# Basic.net
KiCad netlist of a schematic drawn in EAGLE
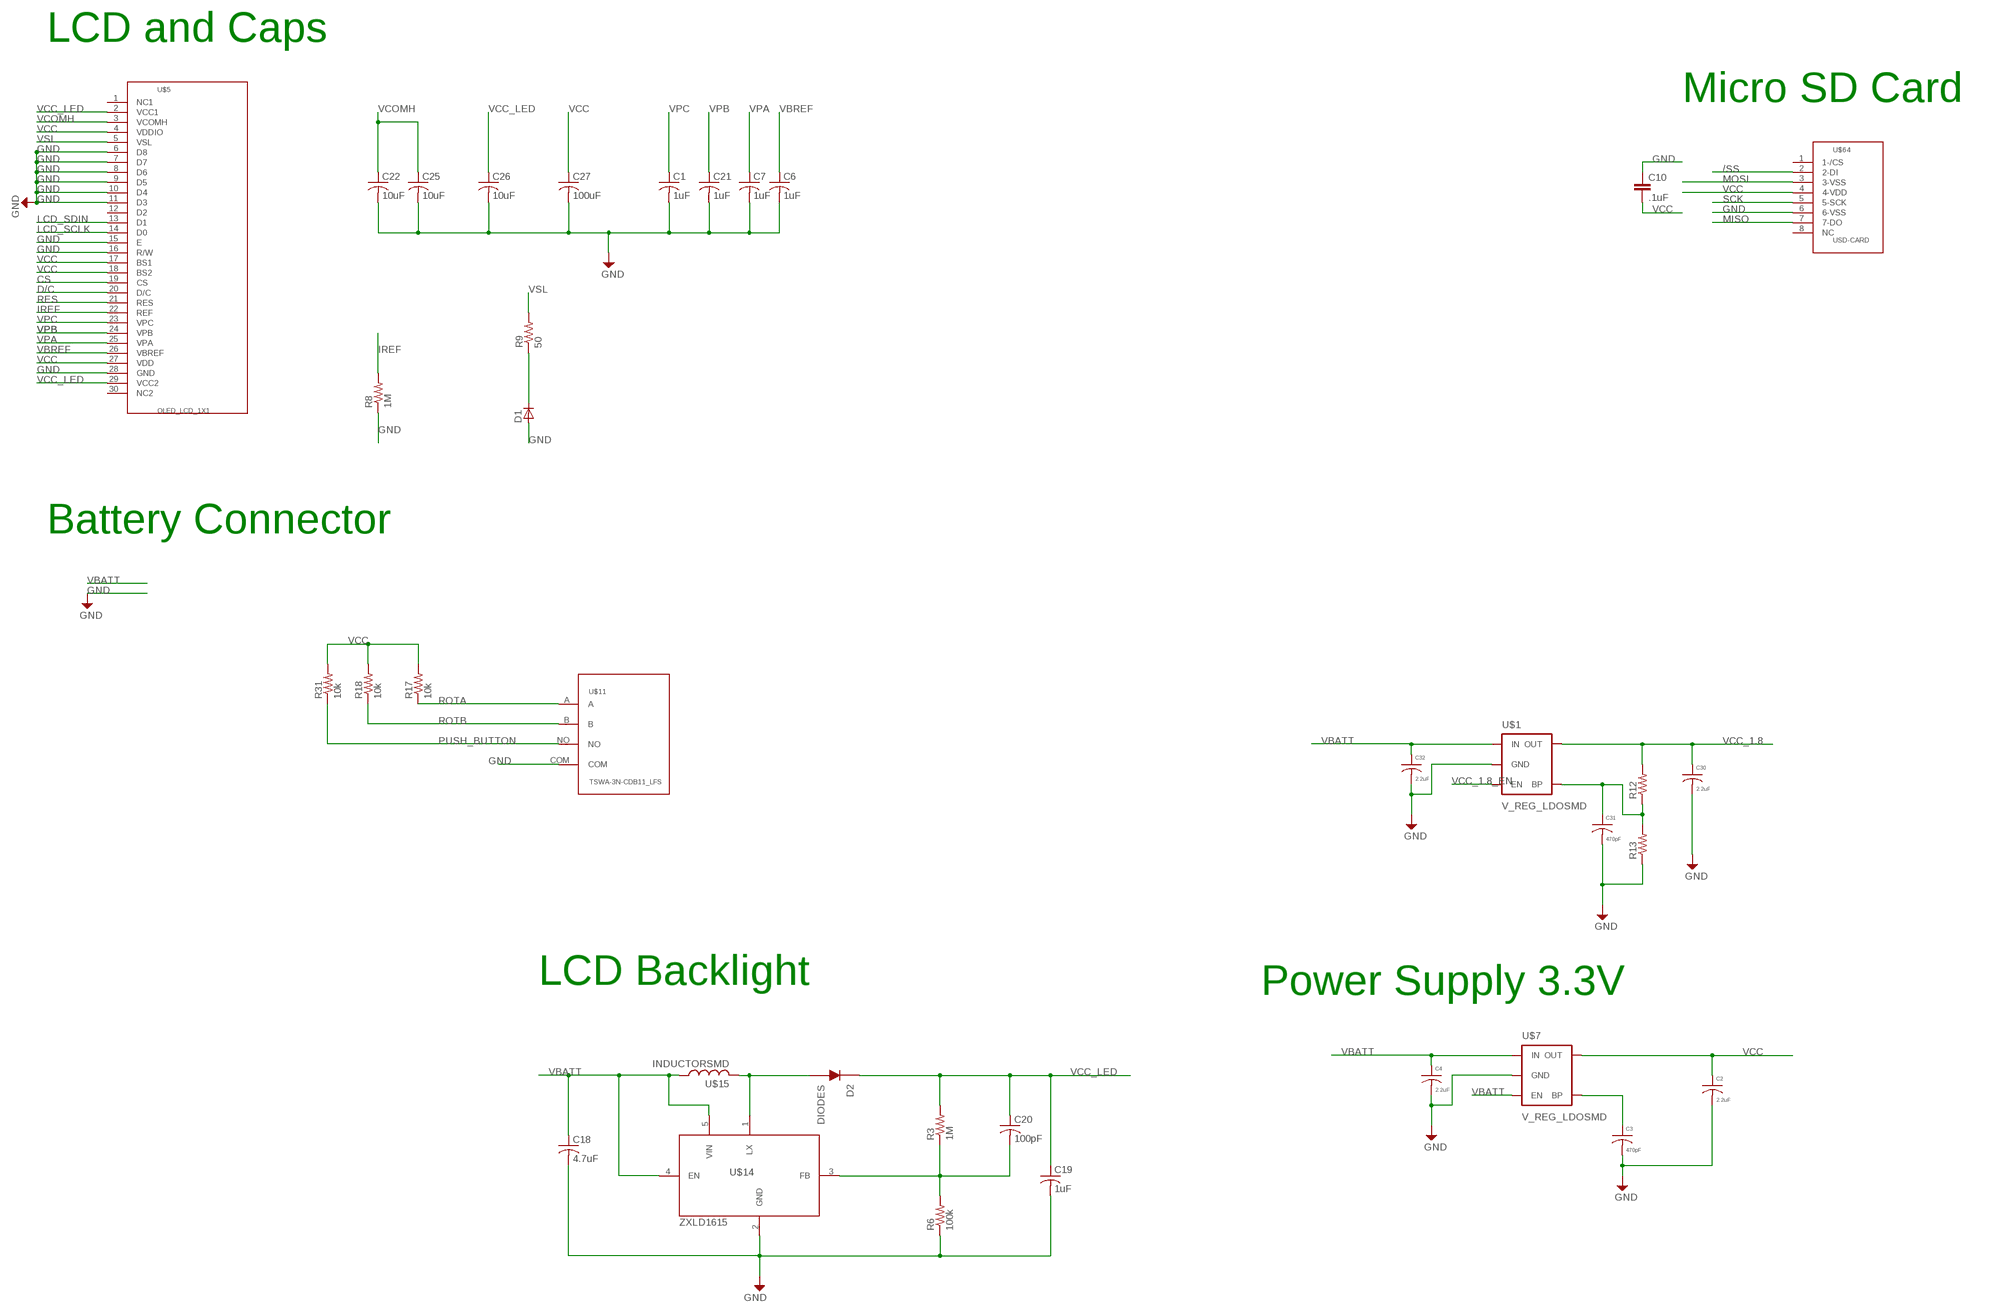
[diagram p0: schematic, sheet 1]
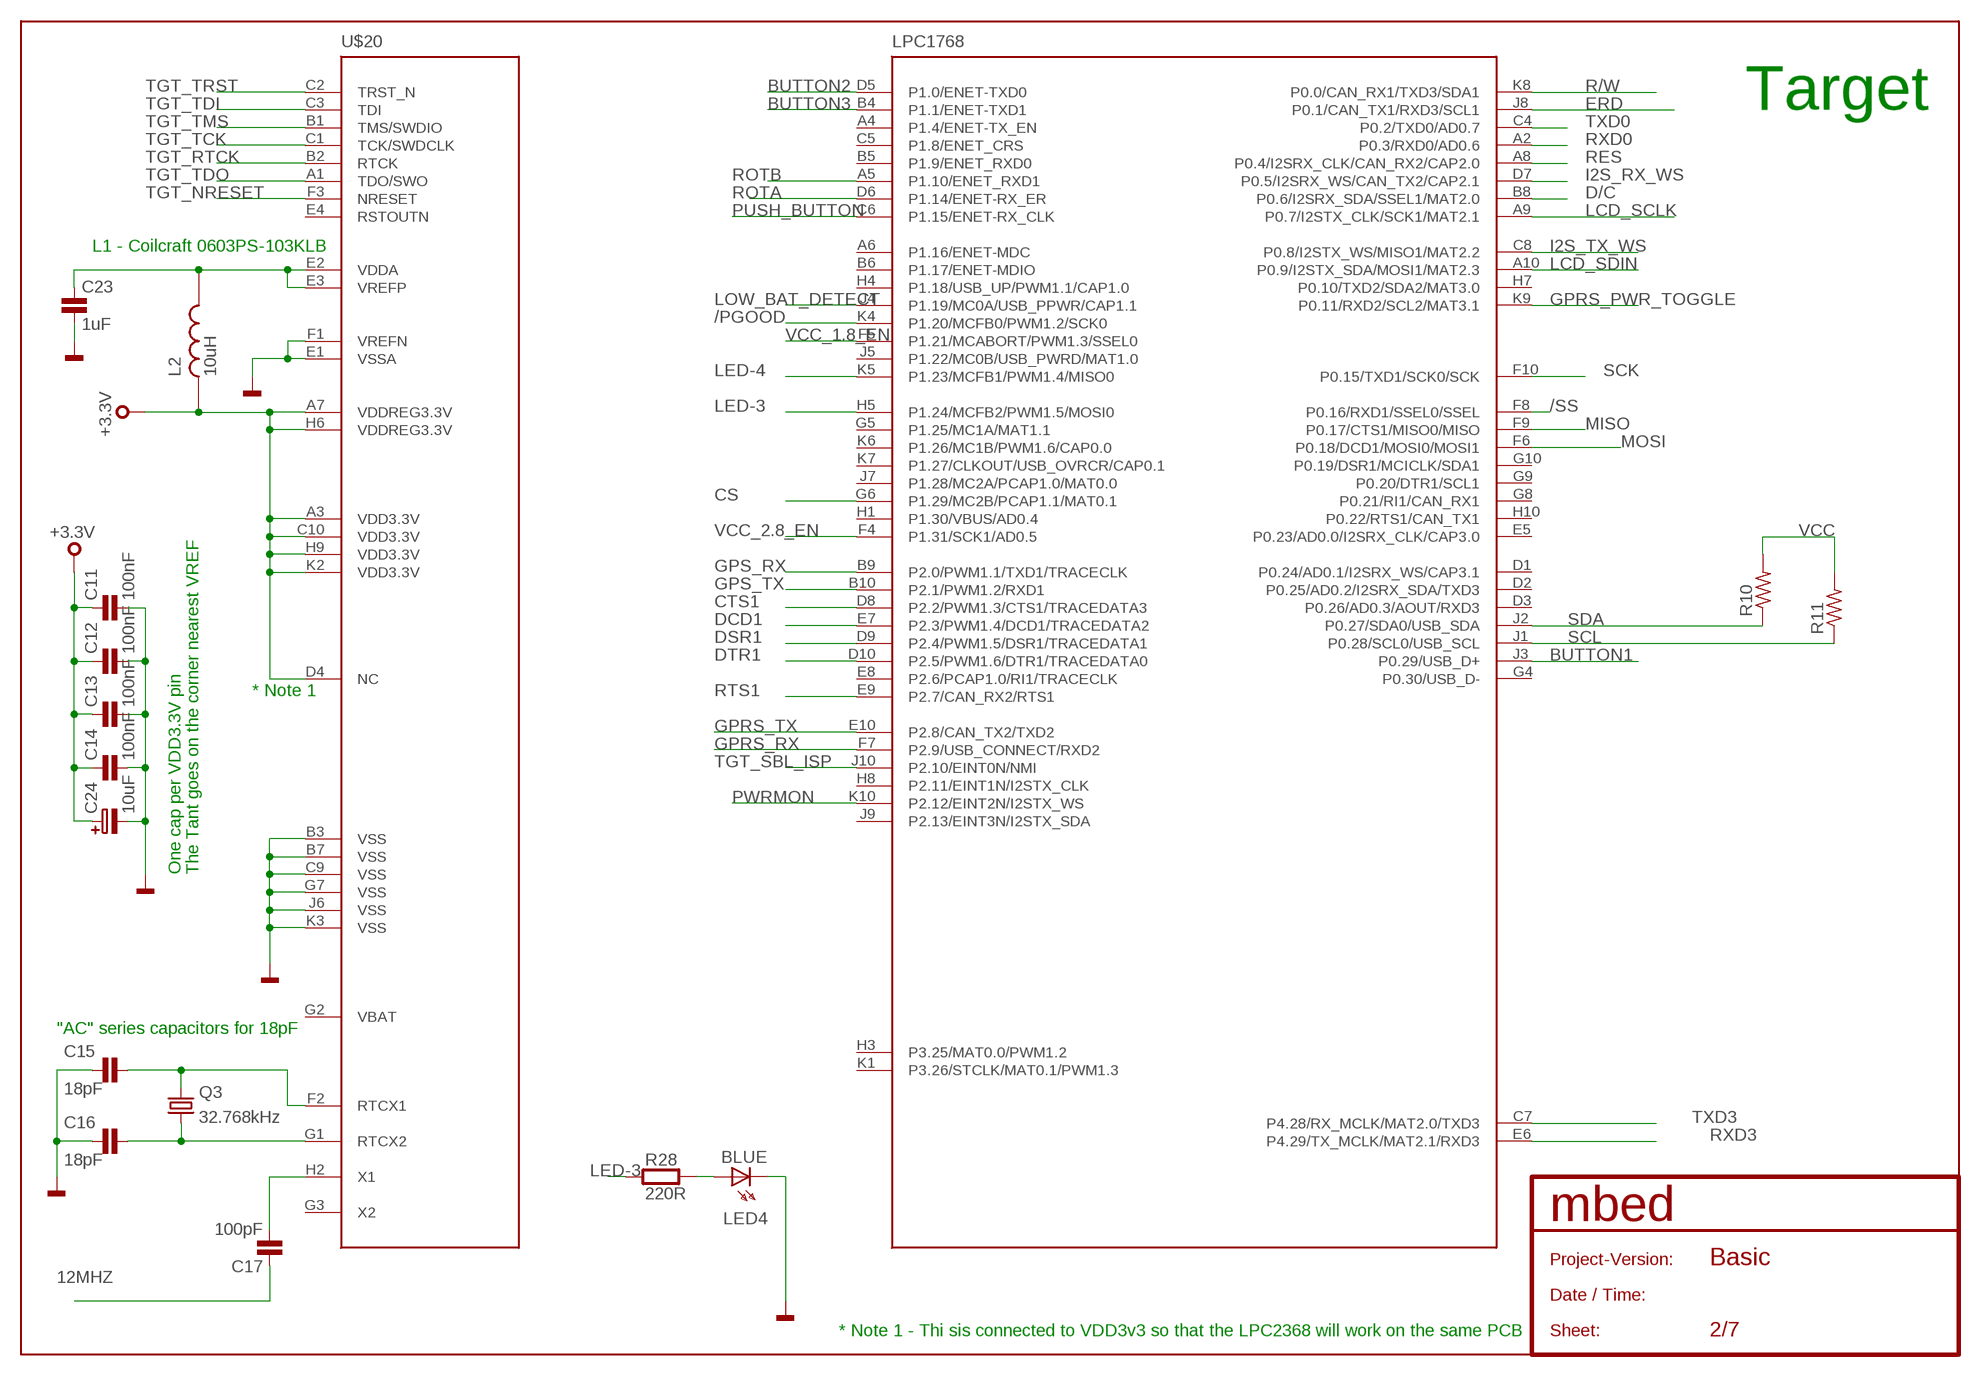
[diagram p1: schematic, sheet 2]
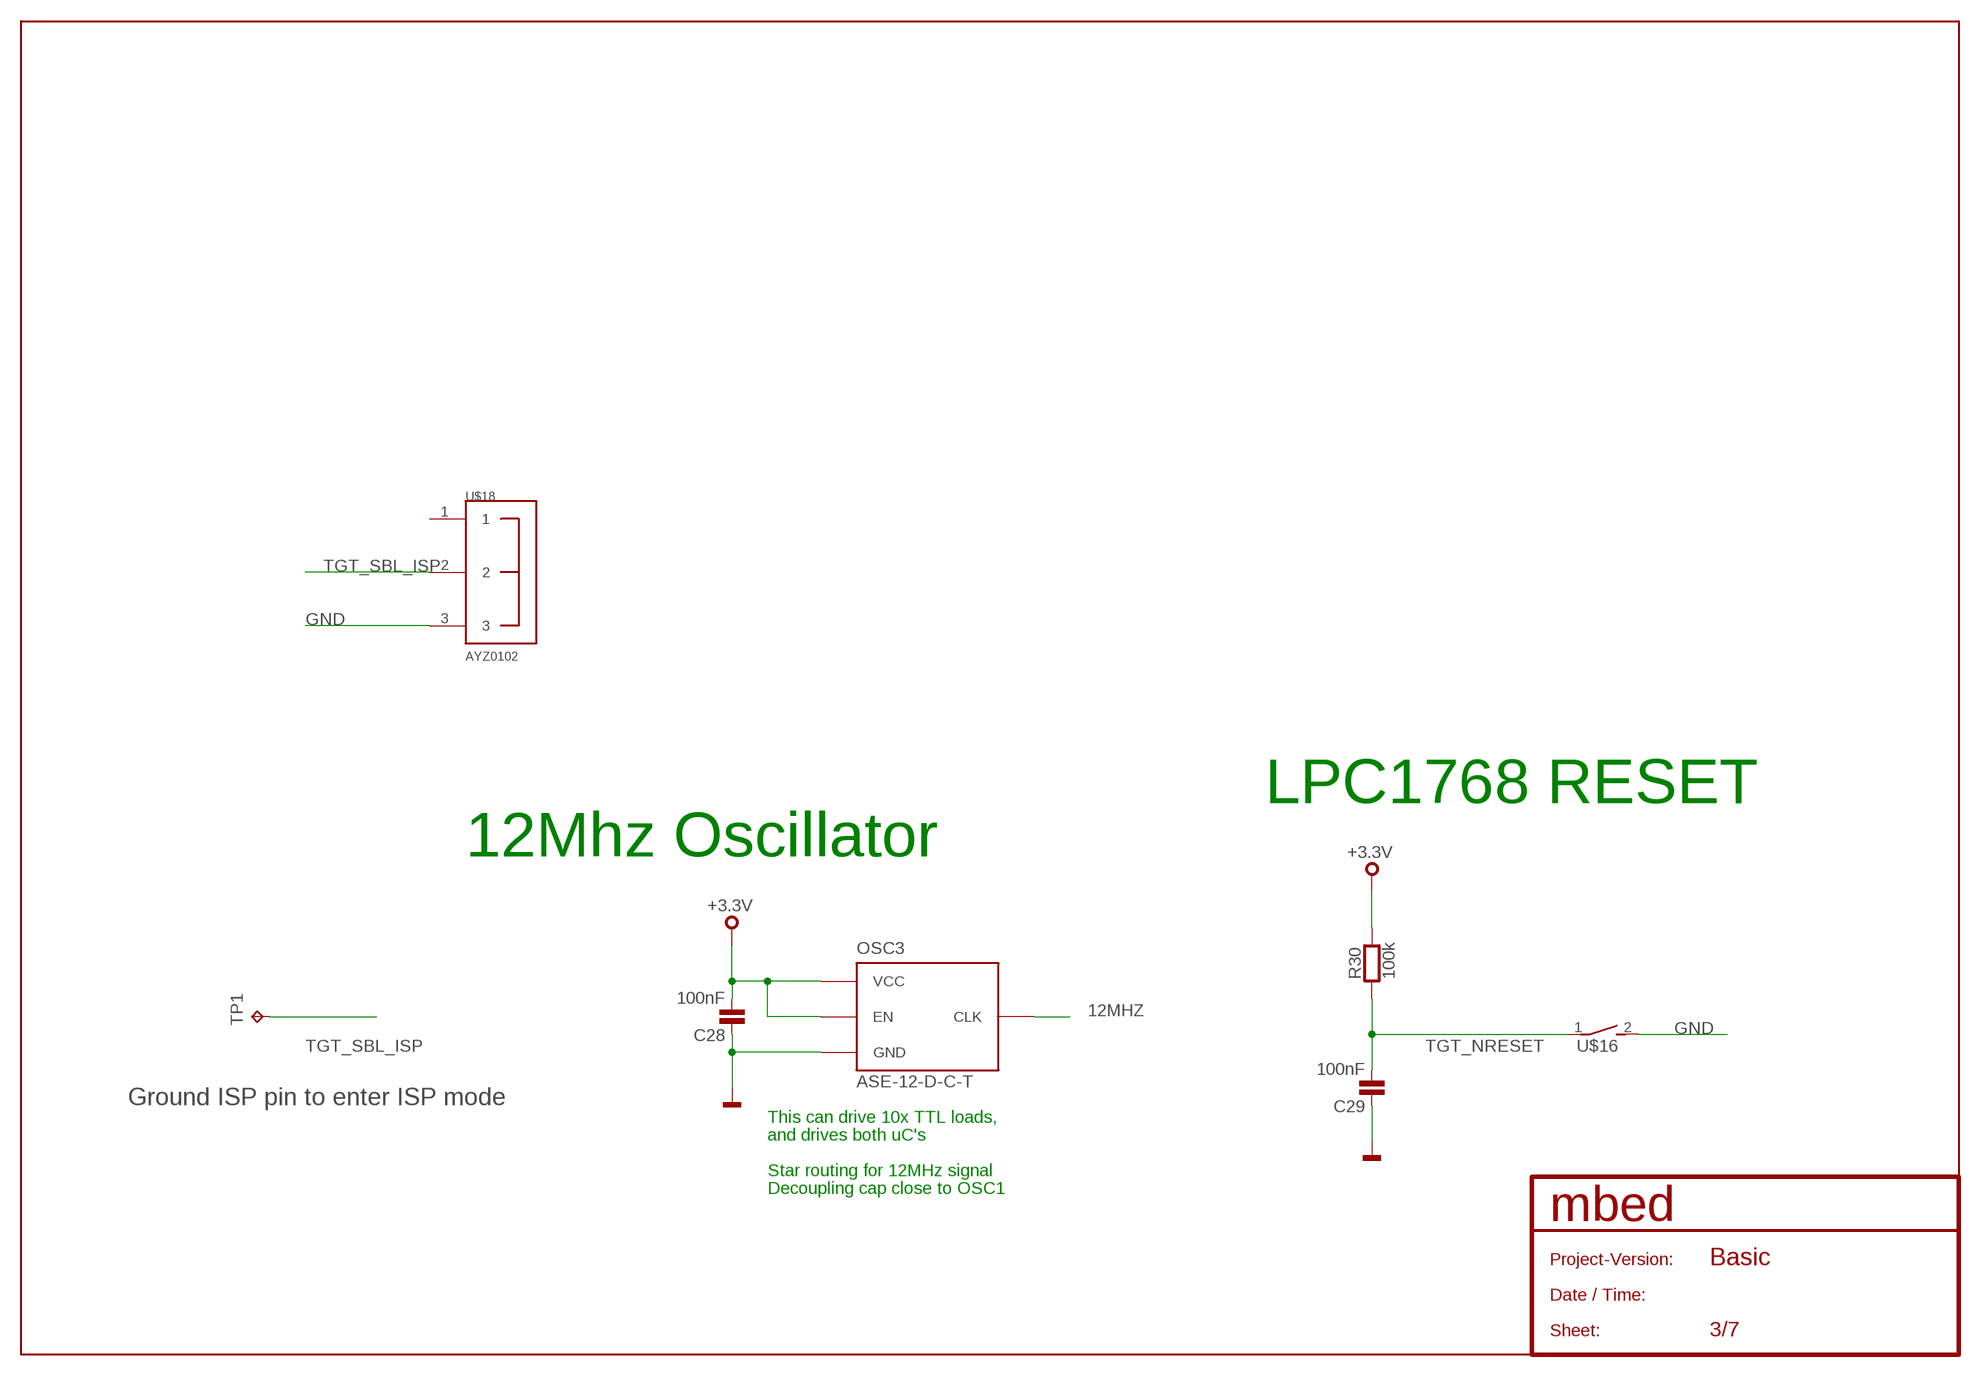
[diagram p2: schematic, sheet 3]
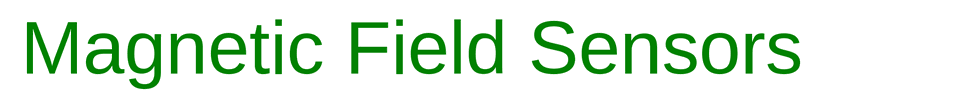
[diagram p3: schematic, sheet 5]
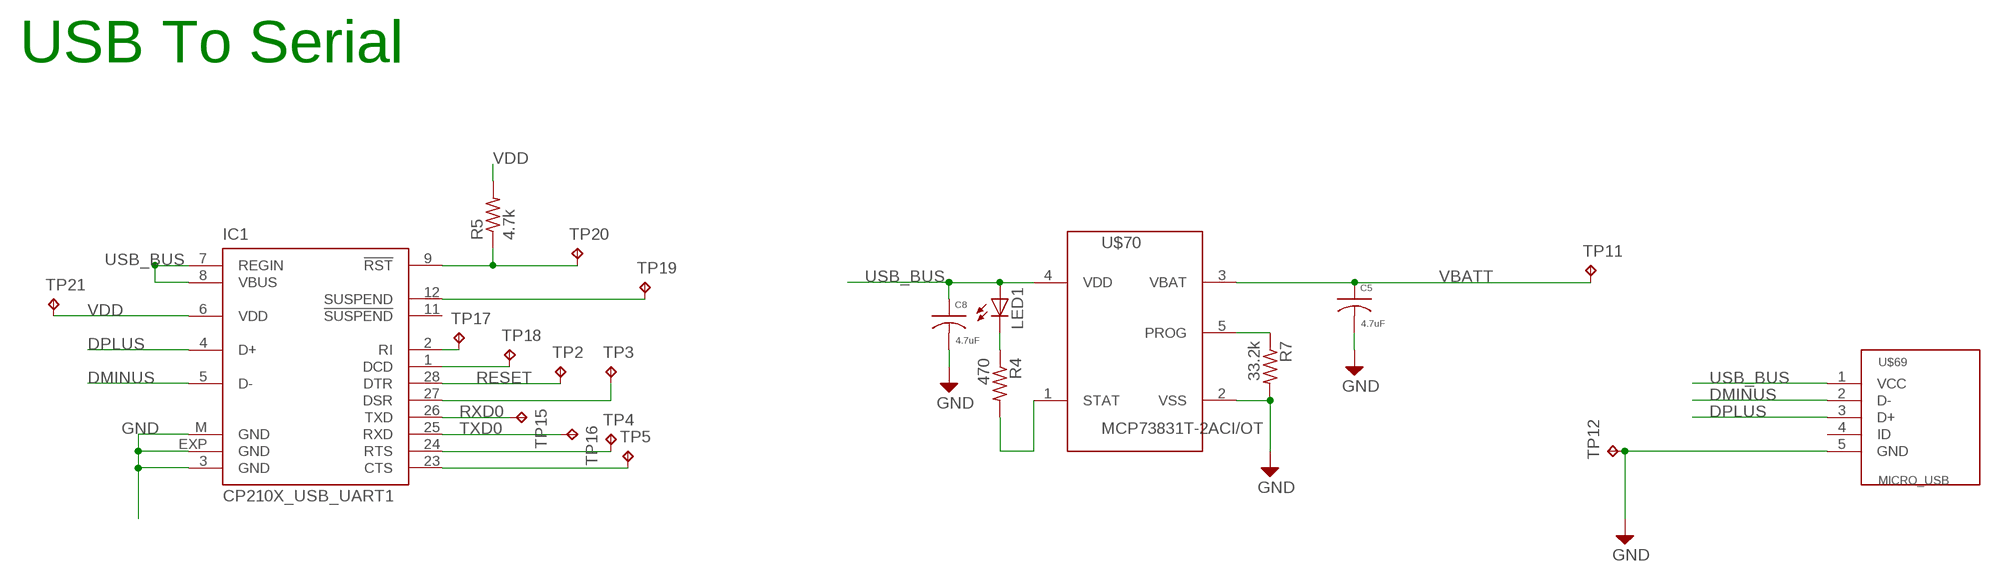
[diagram p4: schematic, sheet 6]
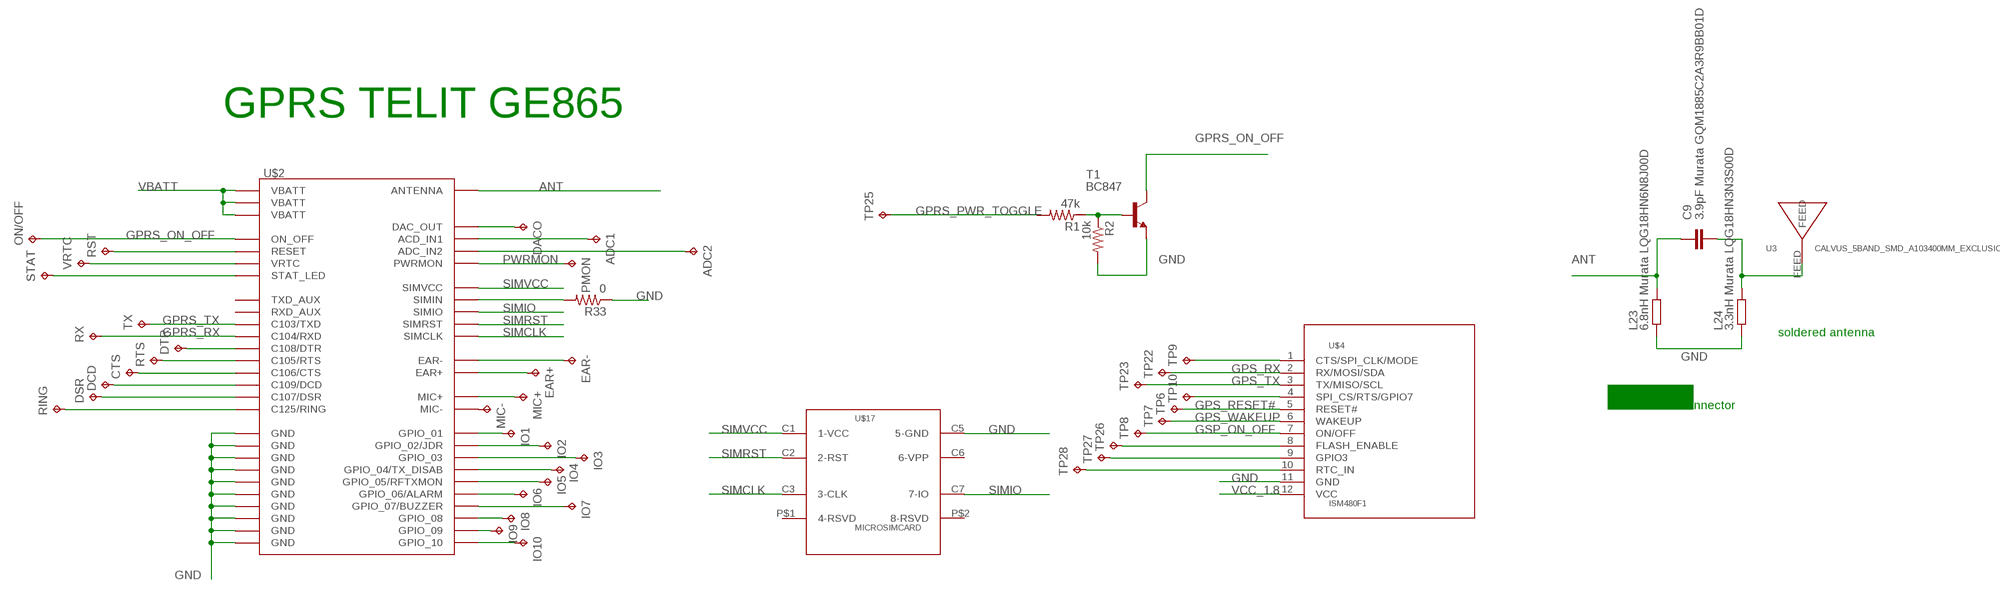
[diagram p5: schematic, sheet 7]

(export (version "E")
  (design (tool "Eeschema 10.0.6"))
  (components
    (comp (ref "C1")
      (value "1uF")
      (footprint "eagle-import:C0402")
      (libsource (lib "eagle-import") (part "C-USC0402"))
    )
    (comp (ref "C2")
      (value "2.2uF")
      (footprint "eagle-import:C0402")
      (libsource (lib "eagle-import") (part "qualified_1_C0402"))
    )
    (comp (ref "C3")
      (value "470pF")
      (footprint "eagle-import:C0402")
      (libsource (lib "eagle-import") (part "qualified_1_C0402"))
    )
    (comp (ref "C4")
      (value "2.2uF")
      (footprint "eagle-import:C0402")
      (libsource (lib "eagle-import") (part "qualified_1_C0402"))
    )
    (comp (ref "C6")
      (value "1uF")
      (footprint "eagle-import:C0402")
      (libsource (lib "eagle-import") (part "C-USC0402"))
    )
    (comp (ref "C7")
      (value "1uF")
      (footprint "eagle-import:C0402")
      (libsource (lib "eagle-import") (part "C-USC0402"))
    )
    (comp (ref "C10")
      (value ".1uF")
      (footprint "eagle-import:C0402")
      (libsource (lib "eagle-import") (part "rcl_C-EUC0402"))
    )
    (comp (ref "C18")
      (value "4.7uF")
      (footprint "eagle-import:C0805K")
      (libsource (lib "eagle-import") (part "C-USC0805K"))
    )
    (comp (ref "C19")
      (value "1uF")
      (footprint "eagle-import:C1206")
      (libsource (lib "eagle-import") (part "C-USC1206"))
    )
    (comp (ref "C20")
      (value "100pF")
      (footprint "eagle-import:C0402")
      (libsource (lib "eagle-import") (part "C-USC0402"))
    )
    (comp (ref "C21")
      (value "1uF")
      (footprint "eagle-import:C0402")
      (libsource (lib "eagle-import") (part "C-USC0402"))
    )
    (comp (ref "C22")
      (value "10uF")
      (footprint "eagle-import:C0603")
      (libsource (lib "eagle-import") (part "C-USC0603"))
    )
    (comp (ref "C25")
      (value "10uF")
      (footprint "eagle-import:C0603")
      (libsource (lib "eagle-import") (part "C-USC0603"))
    )
    (comp (ref "C26")
      (value "10uF")
      (footprint "eagle-import:C0603")
      (libsource (lib "eagle-import") (part "C-USC0603"))
    )
    (comp (ref "C27")
      (value "100uF")
      (footprint "eagle-import:C0603")
      (libsource (lib "eagle-import") (part "C-USC0603"))
    )
    (comp (ref "C30")
      (value "2.2uF")
      (footprint "eagle-import:C0603")
      (libsource (lib "eagle-import") (part "qualified_1_C0603"))
    )
    (comp (ref "C31")
      (value "470pF")
      (footprint "eagle-import:C0402")
      (libsource (lib "eagle-import") (part "qualified_1_C0402"))
    )
    (comp (ref "C32")
      (value "2.2uF")
      (footprint "eagle-import:C0603")
      (libsource (lib "eagle-import") (part "qualified_1_C0603"))
    )
    (comp (ref "D1")
      (value "D-SOD123")
      (footprint "eagle-import:SOD123")
      (libsource (lib "eagle-import") (part "D-SOD123"))
    )
    (comp (ref "D2")
      (value "DIODES")
      (footprint "eagle-import:SOD-123")
      (libsource (lib "eagle-import") (part "DIODES"))
    )
    (comp (ref "R3")
      (value "1M")
      (footprint "eagle-import:R0805")
      (libsource (lib "eagle-import") (part "R-US_R0805"))
    )
    (comp (ref "R6")
      (value "100k")
      (footprint "eagle-import:R0805")
      (libsource (lib "eagle-import") (part "R-US_R0805"))
    )
    (comp (ref "R8")
      (value "1M")
      (footprint "eagle-import:R0603")
      (libsource (lib "eagle-import") (part "R-US_R0603"))
    )
    (comp (ref "R9")
      (value "50")
      (footprint "eagle-import:R0603")
      (libsource (lib "eagle-import") (part "R-US_R0603"))
    )
    (comp (ref "R12")
      (value "R-US_R0402")
      (footprint "eagle-import:R0402")
      (libsource (lib "eagle-import") (part "R-US_R0402"))
    )
    (comp (ref "R13")
      (value "R-US_R0402")
      (footprint "eagle-import:R0402")
      (libsource (lib "eagle-import") (part "R-US_R0402"))
    )
    (comp (ref "R17")
      (value "10k")
      (footprint "eagle-import:R0402")
      (libsource (lib "eagle-import") (part "R-US_R0402"))
    )
    (comp (ref "R18")
      (value "10k")
      (footprint "eagle-import:R0402")
      (libsource (lib "eagle-import") (part "R-US_R0402"))
    )
    (comp (ref "R31")
      (value "10k")
      (footprint "eagle-import:R0402")
      (libsource (lib "eagle-import") (part "R-US_R0402"))
    )
    (comp (ref "U$1")
      (value "V_REG_LDOSMD")
      (footprint "eagle-import:SOT23-5")
      (libsource (lib "eagle-import") (part "V_REG_LDOSMD"))
    )
    (comp (ref "U$5")
      (value "OLED_LCD_1X1")
      (footprint "eagle-import:30ZIF")
      (libsource (lib "eagle-import") (part "OLED_LCD_1X1"))
    )
    (comp (ref "U$7")
      (value "V_REG_LDOSMD")
      (footprint "eagle-import:SOT23-5")
      (libsource (lib "eagle-import") (part "V_REG_LDOSMD"))
    )
    (comp (ref "U$11")
      (value "TSWA-3N-CDB11_LFS")
      (footprint "eagle-import:TSWA-3N-CB11_LFS")
      (libsource (lib "eagle-import") (part "TSWA-3N-CDB11_LFS"))
    )
    (comp (ref "U$14")
      (value "ZXLD1615")
      (footprint "eagle-import:SOT23-5L")
      (libsource (lib "eagle-import") (part "ZXLD1615"))
    )
    (comp (ref "U$15")
      (value "INDUCTORSMD")
      (footprint "eagle-import:INDUCTORSMD1")
      (libsource (lib "eagle-import") (part "INDUCTORSMD"))
    )
    (comp (ref "U$64")
      (value "USD-CARD")
      (footprint "eagle-import:502774-0891")
      (libsource (lib "eagle-import") (part "USD-CARD"))
    )
    (comp (ref "C11")
      (value "100nF")
      (footprint "eagle-import:0402")
      (libsource (lib "eagle-import") (part "C0402"))
    )
    (comp (ref "C12")
      (value "100nF")
      (footprint "eagle-import:0402")
      (libsource (lib "eagle-import") (part "C0402"))
    )
    (comp (ref "C13")
      (value "100nF")
      (footprint "eagle-import:0402")
      (libsource (lib "eagle-import") (part "C0402"))
    )
    (comp (ref "C14")
      (value "100nF")
      (footprint "eagle-import:0402")
      (libsource (lib "eagle-import") (part "C0402"))
    )
    (comp (ref "C15")
      (value "18pF")
      (footprint "eagle-import:0402")
      (libsource (lib "eagle-import") (part "C0402"))
    )
    (comp (ref "C16")
      (value "18pF")
      (footprint "eagle-import:0402")
      (libsource (lib "eagle-import") (part "C0402"))
    )
    (comp (ref "C17")
      (value "100pF")
      (footprint "eagle-import:0402")
      (libsource (lib "eagle-import") (part "C0402"))
    )
    (comp (ref "C23")
      (value "1uF")
      (footprint "eagle-import:0805")
      (libsource (lib "eagle-import") (part "C0805"))
    )
    (comp (ref "C24")
      (value "10uF")
      (footprint "eagle-import:C106B")
      (libsource (lib "eagle-import") (part "C-POLARISEDSMT_TANTALUM"))
    )
    (comp (ref "L2")
      (value "10uH")
      (footprint "eagle-import:L0603")
      (libsource (lib "eagle-import") (part "L_L"))
    )
    (comp (ref "LED4")
      (value "BLUE")
      (footprint "eagle-import:LED_0805")
      (libsource (lib "eagle-import") (part "LED_0805"))
    )
    (comp (ref "Q3")
      (value "32.768kHz")
      (footprint "eagle-import:FC135")
      (libsource (lib "eagle-import") (part "CRYSTALFC135"))
    )
    (comp (ref "R10")
      (value "R-US_R0402")
      (footprint "eagle-import:R0402")
      (libsource (lib "eagle-import") (part "R-US_R0402"))
    )
    (comp (ref "R11")
      (value "R-US_R0402")
      (footprint "eagle-import:R0402")
      (libsource (lib "eagle-import") (part "R-US_R0402"))
    )
    (comp (ref "R28")
      (value "220R")
      (footprint "eagle-import:0402")
      (libsource (lib "eagle-import") (part "R0402"))
    )
    (comp (ref "U$20")
      (value "LPC1768")
      (footprint "eagle-import:TFBGA100")
      (libsource (lib "eagle-import") (part "LPC1768"))
    )
    (comp (ref "C28")
      (value "100nF")
      (footprint "eagle-import:0402")
      (libsource (lib "eagle-import") (part "C0402"))
    )
    (comp (ref "C29")
      (value "100nF")
      (footprint "eagle-import:0402")
      (libsource (lib "eagle-import") (part "C0402"))
    )
    (comp (ref "OSC3")
      (value "ASE-12-D-C-T")
      (footprint "eagle-import:OSC3.2X.2.5")
      (libsource (lib "eagle-import") (part "OSCILLATOR_2.5X3.2"))
    )
    (comp (ref "R30")
      (value "100k")
      (footprint "eagle-import:0402")
      (libsource (lib "eagle-import") (part "R0402"))
    )
    (comp (ref "TP1")
      (value "TPTP09R")
      (footprint "eagle-import:TP09R")
      (libsource (lib "eagle-import") (part "TPTP09R"))
    )
    (comp (ref "U$16")
      (value "RGHT-ANGLE-SMT-SWITCH-688-SKRELF")
      (footprint "eagle-import:2.9X3.9X2.0")
      (libsource (lib "eagle-import") (part "RGHT-ANGLE-SMT-SWITCH-688-SKRELF"))
    )
    (comp (ref "U$18")
      (value "AYZ0102")
      (footprint "eagle-import:AYZ0102")
      (libsource (lib "eagle-import") (part "AYZ0102"))
    )
    (comp (ref "C5")
      (value "4.7uF")
      (footprint "eagle-import:C0603")
      (libsource (lib "eagle-import") (part "qualified_1_C0603"))
    )
    (comp (ref "C8")
      (value "4.7uF")
      (footprint "eagle-import:C0603")
      (libsource (lib "eagle-import") (part "qualified_1_C0603"))
    )
    (comp (ref "IC1")
      (value "CP210X_USB_UART1")
      (footprint "eagle-import:MLP28")
      (libsource (lib "eagle-import") (part "CP210X_USB_UART1"))
    )
    (comp (ref "LED1")
      (value "LEDCHIP-LED0603")
      (footprint "eagle-import:CHIP-LED0603")
      (libsource (lib "eagle-import") (part "LEDCHIP-LED0603"))
    )
    (comp (ref "R4")
      (value "470")
      (footprint "eagle-import:R0402")
      (libsource (lib "eagle-import") (part "R-US_R0402"))
    )
    (comp (ref "R5")
      (value "4.7k")
      (footprint "eagle-import:R0402")
      (libsource (lib "eagle-import") (part "R-US_R0402"))
    )
    (comp (ref "R7")
      (value "33.2k")
      (footprint "eagle-import:R0402")
      (libsource (lib "eagle-import") (part "R-US_R0402"))
    )
    (comp (ref "TP2")
      (value "TPTP06R")
      (footprint "eagle-import:TP06R")
      (libsource (lib "eagle-import") (part "TPTP06R"))
    )
    (comp (ref "TP3")
      (value "TPTP06R")
      (footprint "eagle-import:TP06R")
      (libsource (lib "eagle-import") (part "TPTP06R"))
    )
    (comp (ref "TP4")
      (value "TPTP06R")
      (footprint "eagle-import:TP06R")
      (libsource (lib "eagle-import") (part "TPTP06R"))
    )
    (comp (ref "TP5")
      (value "TPTP06R")
      (footprint "eagle-import:TP06R")
      (libsource (lib "eagle-import") (part "TPTP06R"))
    )
    (comp (ref "TP11")
      (value "TPTP20SQ")
      (footprint "eagle-import:TP20SQ")
      (libsource (lib "eagle-import") (part "TPTP20SQ"))
    )
    (comp (ref "TP12")
      (value "TPTP20SQ")
      (footprint "eagle-import:TP20SQ")
      (libsource (lib "eagle-import") (part "TPTP20SQ"))
    )
    (comp (ref "TP15")
      (value "TPTP06R")
      (footprint "eagle-import:TP06R")
      (libsource (lib "eagle-import") (part "TPTP06R"))
    )
    (comp (ref "TP16")
      (value "TPTP06R")
      (footprint "eagle-import:TP06R")
      (libsource (lib "eagle-import") (part "TPTP06R"))
    )
    (comp (ref "TP17")
      (value "TPTP06R")
      (footprint "eagle-import:TP06R")
      (libsource (lib "eagle-import") (part "TPTP06R"))
    )
    (comp (ref "TP18")
      (value "TPTP06R")
      (footprint "eagle-import:TP06R")
      (libsource (lib "eagle-import") (part "TPTP06R"))
    )
    (comp (ref "TP19")
      (value "TPTP06R")
      (footprint "eagle-import:TP06R")
      (libsource (lib "eagle-import") (part "TPTP06R"))
    )
    (comp (ref "TP20")
      (value "TPTP06R")
      (footprint "eagle-import:TP06R")
      (libsource (lib "eagle-import") (part "TPTP06R"))
    )
    (comp (ref "TP21")
      (value "TPTP06R")
      (footprint "eagle-import:TP06R")
      (libsource (lib "eagle-import") (part "TPTP06R"))
    )
    (comp (ref "U$69")
      (value "MICRO_USB")
      (footprint "eagle-import:MICRO_USB")
      (libsource (lib "eagle-import") (part "MICRO_USB"))
    )
    (comp (ref "U$70")
      (value "MCP73831T-2ACI/OT")
      (footprint "eagle-import:SOT23-5L")
      (libsource (lib "eagle-import") (part "MCP73831T-2ACI/OT"))
    )
    (comp (ref "ADC1")
      (value "TPTP06R")
      (footprint "eagle-import:TP06R")
      (libsource (lib "eagle-import") (part "TPTP06R"))
    )
    (comp (ref "ADC2")
      (value "TPTP06R")
      (footprint "eagle-import:TP06R")
      (libsource (lib "eagle-import") (part "TPTP06R"))
    )
    (comp (ref "C9")
      (value "3.9pF Murata GQM1885C2A3R9BB01D")
      (footprint "eagle-import:C0603-ROUND")
      (libsource (lib "eagle-import") (part "C-EU0603-RND"))
    )
    (comp (ref "CTS")
      (value "TPTP06R")
      (footprint "eagle-import:TP06R")
      (libsource (lib "eagle-import") (part "TPTP06R"))
    )
    (comp (ref "DACO")
      (value "TPTP06R")
      (footprint "eagle-import:TP06R")
      (libsource (lib "eagle-import") (part "TPTP06R"))
    )
    (comp (ref "DCD")
      (value "TPTP06R")
      (footprint "eagle-import:TP06R")
      (libsource (lib "eagle-import") (part "TPTP06R"))
    )
    (comp (ref "DSR")
      (value "TPTP06R")
      (footprint "eagle-import:TP06R")
      (libsource (lib "eagle-import") (part "TPTP06R"))
    )
    (comp (ref "DTR")
      (value "TPTP06R")
      (footprint "eagle-import:TP06R")
      (libsource (lib "eagle-import") (part "TPTP06R"))
    )
    (comp (ref "EAR+")
      (value "TPTP06R")
      (footprint "eagle-import:TP06R")
      (libsource (lib "eagle-import") (part "TPTP06R"))
    )
    (comp (ref "EAR-")
      (value "TPTP06R")
      (footprint "eagle-import:TP06R")
      (libsource (lib "eagle-import") (part "TPTP06R"))
    )
    (comp (ref "IO1")
      (value "TPTP06R")
      (footprint "eagle-import:TP06R")
      (libsource (lib "eagle-import") (part "TPTP06R"))
    )
    (comp (ref "IO2")
      (value "TPTP06R")
      (footprint "eagle-import:TP06R")
      (libsource (lib "eagle-import") (part "TPTP06R"))
    )
    (comp (ref "IO3")
      (value "TPTP06R")
      (footprint "eagle-import:TP06R")
      (libsource (lib "eagle-import") (part "TPTP06R"))
    )
    (comp (ref "IO4")
      (value "TPTP06R")
      (footprint "eagle-import:TP06R")
      (libsource (lib "eagle-import") (part "TPTP06R"))
    )
    (comp (ref "IO5")
      (value "TPTP06R")
      (footprint "eagle-import:TP06R")
      (libsource (lib "eagle-import") (part "TPTP06R"))
    )
    (comp (ref "IO6")
      (value "TPTP06R")
      (footprint "eagle-import:TP06R")
      (libsource (lib "eagle-import") (part "TPTP06R"))
    )
    (comp (ref "IO7")
      (value "TPTP06R")
      (footprint "eagle-import:TP06R")
      (libsource (lib "eagle-import") (part "TPTP06R"))
    )
    (comp (ref "IO8")
      (value "TPTP06R")
      (footprint "eagle-import:TP06R")
      (libsource (lib "eagle-import") (part "TPTP06R"))
    )
    (comp (ref "IO9")
      (value "TPTP06R")
      (footprint "eagle-import:TP06R")
      (libsource (lib "eagle-import") (part "TPTP06R"))
    )
    (comp (ref "IO10")
      (value "TPTP06R")
      (footprint "eagle-import:TP06R")
      (libsource (lib "eagle-import") (part "TPTP06R"))
    )
    (comp (ref "L23")
      (value "6.8nH Murata LQG18HN6N8J00D")
      (footprint "eagle-import:R0603-ROUND")
      (libsource (lib "eagle-import") (part "R-EU_0603-RND"))
    )
    (comp (ref "L24")
      (value "3.3nH Murata LQG18HN3N3S00D")
      (footprint "eagle-import:R0603-ROUND")
      (libsource (lib "eagle-import") (part "R-EU_0603-RND"))
    )
    (comp (ref "MIC+")
      (value "TPTP06R")
      (footprint "eagle-import:TP06R")
      (libsource (lib "eagle-import") (part "TPTP06R"))
    )
    (comp (ref "MIC-")
      (value "TPTP06R")
      (footprint "eagle-import:TP06R")
      (libsource (lib "eagle-import") (part "TPTP06R"))
    )
    (comp (ref "ON/OFF")
      (value "TPTP06R")
      (footprint "eagle-import:TP06R")
      (libsource (lib "eagle-import") (part "TPTP06R"))
    )
    (comp (ref "PMON")
      (value "TPTP06R")
      (footprint "eagle-import:TP06R")
      (libsource (lib "eagle-import") (part "TPTP06R"))
    )
    (comp (ref "R1")
      (value "47k")
      (footprint "eagle-import:R0402")
      (libsource (lib "eagle-import") (part "resistor_R-US_R0402"))
    )
    (comp (ref "R2")
      (value "10k")
      (footprint "eagle-import:R0402")
      (libsource (lib "eagle-import") (part "resistor_R-US_R0402"))
    )
    (comp (ref "R33")
      (value "0")
      (footprint "eagle-import:R0402")
      (libsource (lib "eagle-import") (part "resistor_R-US_R0402"))
    )
    (comp (ref "RING")
      (value "TPTP06R")
      (footprint "eagle-import:TP06R")
      (libsource (lib "eagle-import") (part "TPTP06R"))
    )
    (comp (ref "RST")
      (value "TPTP06R")
      (footprint "eagle-import:TP06R")
      (libsource (lib "eagle-import") (part "TPTP06R"))
    )
    (comp (ref "RTS")
      (value "TPTP06R")
      (footprint "eagle-import:TP06R")
      (libsource (lib "eagle-import") (part "TPTP06R"))
    )
    (comp (ref "RX")
      (value "TPTP06R")
      (footprint "eagle-import:TP06R")
      (libsource (lib "eagle-import") (part "TPTP06R"))
    )
    (comp (ref "STAT")
      (value "TPTP06R")
      (footprint "eagle-import:TP06R")
      (libsource (lib "eagle-import") (part "TPTP06R"))
    )
    (comp (ref "T1")
      (value "BC847")
      (footprint "eagle-import:SOT23")
      (libsource (lib "eagle-import") (part "BC847"))
    )
    (comp (ref "TP6")
      (value "TPTP06R")
      (footprint "eagle-import:TP06R")
      (libsource (lib "eagle-import") (part "TPTP06R"))
    )
    (comp (ref "TP7")
      (value "TPTP06R")
      (footprint "eagle-import:TP06R")
      (libsource (lib "eagle-import") (part "TPTP06R"))
    )
    (comp (ref "TP8")
      (value "TPTP06R")
      (footprint "eagle-import:TP06R")
      (libsource (lib "eagle-import") (part "TPTP06R"))
    )
    (comp (ref "TP9")
      (value "TPTP06R")
      (footprint "eagle-import:TP06R")
      (libsource (lib "eagle-import") (part "TPTP06R"))
    )
    (comp (ref "TP10")
      (value "TPTP06R")
      (footprint "eagle-import:TP06R")
      (libsource (lib "eagle-import") (part "TPTP06R"))
    )
    (comp (ref "TP22")
      (value "TPTP06R")
      (footprint "eagle-import:TP06R")
      (libsource (lib "eagle-import") (part "TPTP06R"))
    )
    (comp (ref "TP23")
      (value "TPTP06R")
      (footprint "eagle-import:TP06R")
      (libsource (lib "eagle-import") (part "TPTP06R"))
    )
    (comp (ref "TP25")
      (value "TPTP06R")
      (footprint "eagle-import:TP06R")
      (libsource (lib "eagle-import") (part "TPTP06R"))
    )
    (comp (ref "TP26")
      (value "TPTP06R")
      (footprint "eagle-import:TP06R")
      (libsource (lib "eagle-import") (part "TPTP06R"))
    )
    (comp (ref "TP27")
      (value "TPTP06R")
      (footprint "eagle-import:TP06R")
      (libsource (lib "eagle-import") (part "TPTP06R"))
    )
    (comp (ref "TP28")
      (value "TPTP06R")
      (footprint "eagle-import:TP06R")
      (libsource (lib "eagle-import") (part "TPTP06R"))
    )
    (comp (ref "TX")
      (value "TPTP06R")
      (footprint "eagle-import:TP06R")
      (libsource (lib "eagle-import") (part "TPTP06R"))
    )
    (comp (ref "U$2")
      (value "GE865")
      (footprint "eagle-import:GE865")
      (libsource (lib "eagle-import") (part "GE865"))
    )
    (comp (ref "U$4")
      (value "ISM480F1")
      (footprint "eagle-import:20488-012E-01")
      (libsource (lib "eagle-import") (part "ISM480F1"))
    )
    (comp (ref "U$17")
      (value "MICROSIMCARD")
      (footprint "eagle-import:FMS006-5000-0")
      (libsource (lib "eagle-import") (part "MICROSIMCARD"))
    )
    (comp (ref "U3")
      (value "CALVUS_5BAND_SMD_A103400MM_EXCLUSION")
      (footprint "eagle-import:CALVUS_5BAND_SMD_A10340_0MM_EXCLUSION")
      (libsource (lib "eagle-import") (part "CALVUS_5BAND_SMD_A103400MM_EXCLUSION"))
    )
    (comp (ref "VRTC")
      (value "TPTP06R")
      (footprint "eagle-import:TP06R")
      (libsource (lib "eagle-import") (part "TPTP06R"))
    )
  )
  (nets
    (net (code "1") (name "12MHZ") (class "Default")
      (node (ref "C17") (pin "1") (pinfunction "P$1_1") (pintype "passive"))
      (node (ref "OSC3") (pin "P$3") (pinfunction "CLK_P$3") (pintype "bidirectional"))
    )
    (net (code "2") (name "ANT") (class "Default")
      (node (ref "C9") (pin "1") (pinfunction "1_1") (pintype "passive"))
      (node (ref "L23") (pin "2") (pinfunction "2_2") (pintype "passive"))
      (node (ref "U$2") (pin "H5") (pinfunction "ANTENNA_H5") (pintype "bidirectional"))
    )
    (net (code "3") (name "BUTTON1") (class "Default")
      (node (ref "U$20") (pin "J3") (pinfunction "P0.29/USB_D+_J3") (pintype "bidirectional"))
    )
    (net (code "4") (name "BUTTON2") (class "Default")
      (node (ref "U$20") (pin "D5") (pinfunction "P1.0/ENET-TXD0_D5") (pintype "bidirectional"))
    )
    (net (code "5") (name "BUTTON3") (class "Default")
      (node (ref "U$20") (pin "B4") (pinfunction "P1.1/ENET-TXD1_B4") (pintype "bidirectional"))
    )
    (net (code "6") (name "CS") (class "Default")
      (node (ref "U$20") (pin "G6") (pinfunction "P1.29/MC2B/PCAP1.1/MAT0.1_G6") (pintype "bidirectional"))
      (node (ref "U$5") (pin "19") (pinfunction "CS_19") (pintype "bidirectional"))
    )
    (net (code "7") (name "CTS1") (class "Default")
      (node (ref "U$20") (pin "D8") (pinfunction "P2.2/PWM1.3/CTS1/TRACEDATA3_D8") (pintype "bidirectional"))
    )
    (net (code "8") (name "DCD1") (class "Default")
      (node (ref "U$20") (pin "E7") (pinfunction "P2.3/PWM1.4/DCD1/TRACEDATA2_E7") (pintype "bidirectional"))
    )
    (net (code "9") (name "DMINUS") (class "Default")
      (node (ref "IC1") (pin "5") (pinfunction "D-_5") (pintype "bidirectional"))
      (node (ref "U$69") (pin "2") (pinfunction "D-_2") (pintype "bidirectional"))
    )
    (net (code "10") (name "DPLUS") (class "Default")
      (node (ref "IC1") (pin "4") (pinfunction "D+_4") (pintype "bidirectional"))
      (node (ref "U$69") (pin "3") (pinfunction "D+_3") (pintype "bidirectional"))
    )
    (net (code "11") (name "DSR1") (class "Default")
      (node (ref "U$20") (pin "D9") (pinfunction "P2.4/PWM1.5/DSR1/TRACEDATA1_D9") (pintype "bidirectional"))
    )
    (net (code "12") (name "DTR1") (class "Default")
      (node (ref "U$20") (pin "D10") (pinfunction "P2.5/PWM1.6/DTR1/TRACEDATA0_D10") (pintype "bidirectional"))
    )
    (net (code "13") (name "D{slash}C") (class "Default")
      (node (ref "U$20") (pin "B8") (pinfunction "P0.6/I2SRX_SDA/SSEL1/MAT2.0_B8") (pintype "bidirectional"))
      (node (ref "U$5") (pin "20") (pinfunction "D/C_20") (pintype "bidirectional"))
    )
    (net (code "14") (name "ERD") (class "Default")
      (node (ref "U$20") (pin "J8") (pinfunction "P0.1/CAN_TX1/RXD3/SCL1_J8") (pintype "bidirectional"))
    )
    (net (code "15") (name "GND") (class "Default")
      (node (ref "C1") (pin "2") (pinfunction "2_2") (pintype "passive"))
      (node (ref "C10") (pin "1") (pinfunction "1_1") (pintype "passive"))
      (node (ref "C11") (pin "2") (pinfunction "P$2_2") (pintype "passive"))
      (node (ref "C12") (pin "2") (pinfunction "P$2_2") (pintype "passive"))
      (node (ref "C13") (pin "2") (pinfunction "P$2_2") (pintype "passive"))
      (node (ref "C14") (pin "2") (pinfunction "P$2_2") (pintype "passive"))
      (node (ref "C15") (pin "1") (pinfunction "P$1_1") (pintype "passive"))
      (node (ref "C16") (pin "1") (pinfunction "P$1_1") (pintype "passive"))
      (node (ref "C18") (pin "2") (pinfunction "2_2") (pintype "passive"))
      (node (ref "C19") (pin "2") (pinfunction "2_2") (pintype "passive"))
      (node (ref "C2") (pin "2") (pinfunction "2_2") (pintype "passive"))
      (node (ref "C21") (pin "2") (pinfunction "2_2") (pintype "passive"))
      (node (ref "C22") (pin "2") (pinfunction "2_2") (pintype "passive"))
      (node (ref "C23") (pin "2") (pinfunction "P$2_2") (pintype "passive"))
      (node (ref "C24") (pin "2") (pinfunction "2_2") (pintype "passive"))
      (node (ref "C25") (pin "2") (pinfunction "2_2") (pintype "passive"))
      (node (ref "C26") (pin "2") (pinfunction "2_2") (pintype "passive"))
      (node (ref "C27") (pin "2") (pinfunction "2_2") (pintype "passive"))
      (node (ref "C28") (pin "1") (pinfunction "P$1_1") (pintype "passive"))
      (node (ref "C29") (pin "1") (pinfunction "P$1_1") (pintype "passive"))
      (node (ref "C3") (pin "2") (pinfunction "2_2") (pintype "passive"))
      (node (ref "C30") (pin "2") (pinfunction "2_2") (pintype "passive"))
      (node (ref "C31") (pin "2") (pinfunction "2_2") (pintype "passive"))
      (node (ref "C32") (pin "2") (pinfunction "2_2") (pintype "passive"))
      (node (ref "C4") (pin "2") (pinfunction "2_2") (pintype "passive"))
      (node (ref "C5") (pin "2") (pinfunction "2_2") (pintype "passive"))
      (node (ref "C6") (pin "2") (pinfunction "2_2") (pintype "passive"))
      (node (ref "C7") (pin "2") (pinfunction "2_2") (pintype "passive"))
      (node (ref "C8") (pin "2") (pinfunction "2_2") (pintype "passive"))
      (node (ref "D1") (pin "2") (pinfunction "A_2") (pintype "passive"))
      (node (ref "IC1") (pin "3") (pinfunction "GND_3") (pintype "power_in"))
      (node (ref "IC1") (pin "EXP") (pinfunction "GND_EXP") (pintype "power_in"))
      (node (ref "IC1") (pin "M") (pinfunction "GND_M") (pintype "power_in"))
      (node (ref "L23") (pin "1") (pinfunction "1_1") (pintype "passive"))
      (node (ref "L24") (pin "1") (pinfunction "1_1") (pintype "passive"))
      (node (ref "LED4") (pin "K") (pinfunction "K_K") (pintype "passive"))
      (node (ref "OSC3") (pin "P$2") (pinfunction "GND_P$2") (pintype "bidirectional"))
      (node (ref "R13") (pin "1") (pinfunction "1_1") (pintype "passive"))
      (node (ref "R2") (pin "2") (pinfunction "2_2") (pintype "passive"))
      (node (ref "R33") (pin "1") (pinfunction "1_1") (pintype "passive"))
      (node (ref "R6") (pin "1") (pinfunction "1_1") (pintype "passive"))
      (node (ref "R7") (pin "2") (pinfunction "2_2") (pintype "passive"))
      (node (ref "R8") (pin "1") (pinfunction "1_1") (pintype "passive"))
      (node (ref "T1") (pin "2") (pinfunction "E_2") (pintype "passive"))
      (node (ref "TP12") (pin "TP") (pinfunction "TP_TP") (pintype "input"))
      (node (ref "U$1") (pin "2") (pinfunction "GND_2") (pintype "input"))
      (node (ref "U$11") (pin "COM") (pinfunction "COM_COM") (pintype "bidirectional"))
      (node (ref "U$14") (pin "2") (pinfunction "GND_2") (pintype "bidirectional"))
      (node (ref "U$16") (pin "2") (pinfunction "2_2") (pintype "passive"))
      (node (ref "U$17") (pin "C5") (pinfunction "5-GND_C5") (pintype "bidirectional"))
      (node (ref "U$18") (pin "3") (pinfunction "3_3") (pintype "bidirectional"))
      (node (ref "U$2") (pin "C2") (pinfunction "GND_C2") (pintype "bidirectional"))
      (node (ref "U$2") (pin "C7") (pinfunction "GND_C7") (pintype "bidirectional"))
      (node (ref "U$2") (pin "E5") (pinfunction "GND_E5") (pintype "bidirectional"))
      (node (ref "U$2") (pin "E7") (pinfunction "GND_E7") (pintype "bidirectional"))
      (node (ref "U$2") (pin "G1") (pinfunction "GND_G1") (pintype "bidirectional"))
      (node (ref "U$2") (pin "G3") (pinfunction "GND_G3") (pintype "bidirectional"))
      (node (ref "U$2") (pin "G4") (pinfunction "GND_G4") (pintype "bidirectional"))
      (node (ref "U$2") (pin "G5") (pinfunction "GND_G5") (pintype "bidirectional"))
      (node (ref "U$2") (pin "H3") (pinfunction "GND_H3") (pintype "bidirectional"))
      (node (ref "U$2") (pin "H6") (pinfunction "GND_H6") (pintype "bidirectional"))
      (node (ref "U$20") (pin "B3") (pinfunction "VSS_B3") (pintype "bidirectional"))
      (node (ref "U$20") (pin "B7") (pinfunction "VSS_B7") (pintype "bidirectional"))
      (node (ref "U$20") (pin "C9") (pinfunction "VSS_C9") (pintype "bidirectional"))
      (node (ref "U$20") (pin "E1") (pinfunction "VSSA_E1") (pintype "bidirectional"))
      (node (ref "U$20") (pin "F1") (pinfunction "VREFN_F1") (pintype "bidirectional"))
      (node (ref "U$20") (pin "G7") (pinfunction "VSS_G7") (pintype "bidirectional"))
      (node (ref "U$20") (pin "J6") (pinfunction "VSS_J6") (pintype "bidirectional"))
      (node (ref "U$20") (pin "K3") (pinfunction "VSS_K3") (pintype "bidirectional"))
      (node (ref "U$4") (pin "11") (pinfunction "GND_11") (pintype "bidirectional"))
      (node (ref "U$5") (pin "10") (pinfunction "D4_10") (pintype "bidirectional"))
      (node (ref "U$5") (pin "11") (pinfunction "D3_11") (pintype "bidirectional"))
      (node (ref "U$5") (pin "15") (pinfunction "E_15") (pintype "bidirectional"))
      (node (ref "U$5") (pin "16") (pinfunction "R/W_16") (pintype "bidirectional"))
      (node (ref "U$5") (pin "28") (pinfunction "GND_28") (pintype "bidirectional"))
      (node (ref "U$5") (pin "6") (pinfunction "D8_6") (pintype "bidirectional"))
      (node (ref "U$5") (pin "7") (pinfunction "D7_7") (pintype "bidirectional"))
      (node (ref "U$5") (pin "8") (pinfunction "D6_8") (pintype "bidirectional"))
      (node (ref "U$5") (pin "9") (pinfunction "D5_9") (pintype "bidirectional"))
      (node (ref "U$64") (pin "6") (pinfunction "6-VSS_6") (pintype "bidirectional"))
      (node (ref "U$69") (pin "5") (pinfunction "GND_5") (pintype "bidirectional"))
      (node (ref "U$7") (pin "2") (pinfunction "GND_2") (pintype "input"))
      (node (ref "U$70") (pin "2") (pinfunction "VSS_2") (pintype "bidirectional"))
    )
    (net (code "16") (name "GPRS_ON_OFF") (class "Default")
      (node (ref "ON/OFF") (pin "TP") (pinfunction "TP_TP") (pintype "input"))
      (node (ref "T1") (pin "3") (pinfunction "C_3") (pintype "passive"))
      (node (ref "U$2") (pin "B1") (pinfunction "ON_OFF_B1") (pintype "bidirectional"))
    )
    (net (code "17") (name "GPRS_PWR_TOGGLE") (class "Default")
      (node (ref "R1") (pin "2") (pinfunction "2_2") (pintype "passive"))
      (node (ref "TP25") (pin "TP") (pinfunction "TP_TP") (pintype "input"))
      (node (ref "U$20") (pin "K9") (pinfunction "P0.11/RXD2/SCL2/MAT3.1_K9") (pintype "bidirectional"))
    )
    (net (code "18") (name "GPRS_RX") (class "Default")
      (node (ref "RX") (pin "TP") (pinfunction "TP_TP") (pintype "input"))
      (node (ref "U$2") (pin "A4") (pinfunction "C104/RXD_A4") (pintype "bidirectional"))
      (node (ref "U$20") (pin "F7") (pinfunction "P2.9/USB_CONNECT/RXD2_F7") (pintype "bidirectional"))
    )
    (net (code "19") (name "GPRS_TX") (class "Default")
      (node (ref "TX") (pin "TP") (pinfunction "TP_TP") (pintype "input"))
      (node (ref "U$2") (pin "A3") (pinfunction "C103/TXD_A3") (pintype "bidirectional"))
      (node (ref "U$20") (pin "E10") (pinfunction "P2.8/CAN_TX2/TXD2_E10") (pintype "bidirectional"))
    )
    (net (code "20") (name "GPS_RESET#") (class "Default")
      (node (ref "TP6") (pin "TP") (pinfunction "TP_TP") (pintype "input"))
      (node (ref "U$4") (pin "5") (pinfunction "RESET#_5") (pintype "bidirectional"))
    )
    (net (code "21") (name "GPS_RX") (class "Default")
      (node (ref "TP22") (pin "TP") (pinfunction "TP_TP") (pintype "input"))
      (node (ref "U$20") (pin "B9") (pinfunction "P2.0/PWM1.1/TXD1/TRACECLK_B9") (pintype "bidirectional"))
      (node (ref "U$4") (pin "2") (pinfunction "RX/MOSI/SDA_2") (pintype "bidirectional"))
    )
    (net (code "22") (name "GPS_TX") (class "Default")
      (node (ref "TP23") (pin "TP") (pinfunction "TP_TP") (pintype "input"))
      (node (ref "U$20") (pin "B10") (pinfunction "P2.1/PWM1.2/RXD1_B10") (pintype "bidirectional"))
      (node (ref "U$4") (pin "3") (pinfunction "TX/MISO/SCL_3") (pintype "bidirectional"))
    )
    (net (code "23") (name "GPS_WAKEUP") (class "Default")
      (node (ref "TP7") (pin "TP") (pinfunction "TP_TP") (pintype "input"))
      (node (ref "U$4") (pin "6") (pinfunction "WAKEUP_6") (pintype "bidirectional"))
    )
    (net (code "24") (name "GSP_ON_OFF") (class "Default")
      (node (ref "TP8") (pin "TP") (pinfunction "TP_TP") (pintype "input"))
      (node (ref "U$4") (pin "7") (pinfunction "ON/OFF_7") (pintype "bidirectional"))
    )
    (net (code "25") (name "I2S_RX_WS") (class "Default")
      (node (ref "U$20") (pin "D7") (pinfunction "P0.5/I2SRX_WS/CAN_TX2/CAP2.1_D7") (pintype "bidirectional"))
    )
    (net (code "26") (name "I2S_TX_WS") (class "Default")
      (node (ref "U$20") (pin "C8") (pinfunction "P0.8/I2STX_WS/MISO1/MAT2.2_C8") (pintype "bidirectional"))
    )
    (net (code "27") (name "IREF") (class "Default")
      (node (ref "R8") (pin "2") (pinfunction "2_2") (pintype "passive"))
      (node (ref "U$5") (pin "22") (pinfunction "REF_22") (pintype "bidirectional"))
    )
    (net (code "28") (name "LCD_SCLK") (class "Default")
      (node (ref "U$20") (pin "A9") (pinfunction "P0.7/I2STX_CLK/SCK1/MAT2.1_A9") (pintype "bidirectional"))
      (node (ref "U$5") (pin "14") (pinfunction "D0_14") (pintype "bidirectional"))
    )
    (net (code "29") (name "LCD_SDIN") (class "Default")
      (node (ref "U$20") (pin "A10") (pinfunction "P0.9/I2STX_SDA/MOSI1/MAT2.3_A10") (pintype "bidirectional"))
      (node (ref "U$5") (pin "13") (pinfunction "D1_13") (pintype "bidirectional"))
    )
    (net (code "30") (name "LED-3") (class "Default")
      (node (ref "R28") (pin "1") (pinfunction "P$1_1") (pintype "passive"))
      (node (ref "U$20") (pin "H5") (pinfunction "P1.24/MCFB2/PWM1.5/MOSI0_H5") (pintype "bidirectional"))
    )
    (net (code "31") (name "LED-4") (class "Default")
      (node (ref "U$20") (pin "K5") (pinfunction "P1.23/MCFB1/PWM1.4/MISO0_K5") (pintype "bidirectional"))
    )
    (net (code "32") (name "LOW_BAT_DETECT") (class "Default")
      (node (ref "U$20") (pin "J4") (pinfunction "P1.19/MC0A/USB_PPWR/CAP1.1_J4") (pintype "bidirectional"))
    )
    (net (code "33") (name "MISO") (class "Default")
      (node (ref "U$20") (pin "F9") (pinfunction "P0.17/CTS1/MISO0/MISO_F9") (pintype "bidirectional"))
      (node (ref "U$64") (pin "7") (pinfunction "7-DO_7") (pintype "bidirectional"))
    )
    (net (code "34") (name "MOSI") (class "Default")
      (node (ref "U$20") (pin "F6") (pinfunction "P0.18/DCD1/MOSI0/MOSI1_F6") (pintype "bidirectional"))
      (node (ref "U$64") (pin "3") (pinfunction "3-VSS_3") (pintype "bidirectional"))
    )
    (net (code "35") (name "Net-(C9-Pad2)") (class "Default")
      (node (ref "C9") (pin "2") (pinfunction "2_2") (pintype "passive"))
      (node (ref "L24") (pin "2") (pinfunction "2_2") (pintype "passive"))
      (node (ref "U3") (pin "FEED") (pinfunction "FEED_FEED") (pintype "bidirectional"))
    )
    (net (code "36") (name "Net-(C15-P$2)") (class "Default")
      (node (ref "C15") (pin "2") (pinfunction "P$2_2") (pintype "passive"))
      (node (ref "Q3") (pin "X2") (pinfunction "2_X2") (pintype "passive"))
      (node (ref "U$20") (pin "F2") (pinfunction "RTCX1_F2") (pintype "bidirectional"))
    )
    (net (code "37") (name "Net-(C16-P$2)") (class "Default")
      (node (ref "C16") (pin "2") (pinfunction "P$2_2") (pintype "passive"))
      (node (ref "Q3") (pin "X1") (pinfunction "1_X1") (pintype "passive"))
      (node (ref "U$20") (pin "G1") (pinfunction "RTCX2_G1") (pintype "bidirectional"))
    )
    (net (code "38") (name "Net-(C17-P$2)") (class "Default")
      (node (ref "C17") (pin "2") (pinfunction "P$2_2") (pintype "passive"))
      (node (ref "U$20") (pin "H2") (pinfunction "X1_H2") (pintype "bidirectional"))
    )
    (net (code "39") (name "Net-(C23-P$1)") (class "Default")
      (node (ref "C23") (pin "1") (pinfunction "P$1_1") (pintype "passive"))
      (node (ref "L2") (pin "P$2") (pinfunction "P$2_P$2") (pintype "bidirectional"))
      (node (ref "U$20") (pin "E2") (pinfunction "VDDA_E2") (pintype "bidirectional"))
      (node (ref "U$20") (pin "E3") (pinfunction "VREFP_E3") (pintype "bidirectional"))
    )
    (net (code "40") (name "Net-(D1-C)") (class "Default")
      (node (ref "D1") (pin "1") (pinfunction "C_1") (pintype "passive"))
      (node (ref "R9") (pin "1") (pinfunction "1_1") (pintype "passive"))
    )
    (net (code "41") (name "Net-(D2-A1)") (class "Default")
      (node (ref "D2") (pin "1") (pinfunction "A1_1") (pintype "passive"))
      (node (ref "U$14") (pin "1") (pinfunction "LX_1") (pintype "bidirectional"))
      (node (ref "U$15") (pin "2") (pinfunction "2_2") (pintype "passive"))
    )
    (net (code "42") (name "Net-(IC1-CTS)") (class "Default")
      (node (ref "IC1") (pin "23") (pinfunction "CTS_23") (pintype "input"))
      (node (ref "TP5") (pin "TP") (pinfunction "TP_TP") (pintype "input"))
    )
    (net (code "43") (name "Net-(IC1-DCD)") (class "Default")
      (node (ref "IC1") (pin "1") (pinfunction "DCD_1") (pintype "input"))
      (node (ref "TP18") (pin "TP") (pinfunction "TP_TP") (pintype "input"))
    )
    (net (code "44") (name "Net-(IC1-DSR)") (class "Default")
      (node (ref "IC1") (pin "27") (pinfunction "DSR_27") (pintype "input"))
      (node (ref "TP3") (pin "TP") (pinfunction "TP_TP") (pintype "input"))
    )
    (net (code "45") (name "Net-(IC1-RI)") (class "Default")
      (node (ref "IC1") (pin "2") (pinfunction "RI_2") (pintype "input"))
      (node (ref "TP17") (pin "TP") (pinfunction "TP_TP") (pintype "input"))
    )
    (net (code "46") (name "Net-(IC1-RTS)") (class "Default")
      (node (ref "IC1") (pin "24") (pinfunction "RTS_24") (pintype "output"))
      (node (ref "TP4") (pin "TP") (pinfunction "TP_TP") (pintype "input"))
    )
    (net (code "47") (name "Net-(IC1-SUSPEND)") (class "Default")
      (node (ref "IC1") (pin "12") (pinfunction "SUSPEND_12") (pintype "output"))
      (node (ref "TP19") (pin "TP") (pinfunction "TP_TP") (pintype "input"))
    )
    (net (code "48") (name "Net-(IC1-~{RST})") (class "Default")
      (node (ref "IC1") (pin "9") (pinfunction "~{RST}_9") (pintype "bidirectional"))
      (node (ref "R5") (pin "1") (pinfunction "1_1") (pintype "passive"))
      (node (ref "TP20") (pin "TP") (pinfunction "TP_TP") (pintype "input"))
    )
    (net (code "49") (name "Net-(LED1-PadC)") (class "Default")
      (node (ref "LED1") (pin "C") (pinfunction "C_C") (pintype "passive"))
      (node (ref "R4") (pin "1") (pinfunction "1_1") (pintype "passive"))
    )
    (net (code "50") (name "Net-(R28-P$2)") (class "Default")
      (node (ref "LED4") (pin "A") (pinfunction "A_A") (pintype "passive"))
      (node (ref "R28") (pin "2") (pinfunction "P$2_2") (pintype "passive"))
    )
    (net (code "51") (name "Net-(T1-B)") (class "Default")
      (node (ref "R1") (pin "1") (pinfunction "1_1") (pintype "passive"))
      (node (ref "R2") (pin "1") (pinfunction "1_1") (pintype "passive"))
      (node (ref "T1") (pin "1") (pinfunction "B_1") (pintype "passive"))
    )
    (net (code "52") (name "Net-(U$1-BP)") (class "Default")
      (node (ref "C31") (pin "1") (pinfunction "1_1") (pintype "passive"))
      (node (ref "R12") (pin "1") (pinfunction "1_1") (pintype "passive"))
      (node (ref "R13") (pin "2") (pinfunction "2_2") (pintype "passive"))
      (node (ref "U$1") (pin "4") (pinfunction "BP_4") (pintype "input"))
    )
    (net (code "53") (name "Net-(U$2-ACD_IN1)") (class "Default")
      (node (ref "ADC1") (pin "TP") (pinfunction "TP_TP") (pintype "input"))
      (node (ref "U$2") (pin "F5") (pinfunction "ACD_IN1_F5") (pintype "bidirectional"))
    )
    (net (code "54") (name "Net-(U$2-ADC_IN2)") (class "Default")
      (node (ref "ADC2") (pin "TP") (pinfunction "TP_TP") (pintype "input"))
      (node (ref "U$2") (pin "F6") (pinfunction "ADC_IN2_F6") (pintype "bidirectional"))
    )
    (net (code "55") (name "Net-(U$2-C105{slash}RTS)") (class "Default")
      (node (ref "RTS") (pin "TP") (pinfunction "TP_TP") (pintype "input"))
      (node (ref "U$2") (pin "A1") (pinfunction "C105/RTS_A1") (pintype "bidirectional"))
    )
    (net (code "56") (name "Net-(U$2-C106{slash}CTS)") (class "Default")
      (node (ref "CTS") (pin "TP") (pinfunction "TP_TP") (pintype "input"))
      (node (ref "U$2") (pin "A2") (pinfunction "C106/CTS_A2") (pintype "bidirectional"))
    )
    (net (code "57") (name "Net-(U$2-C107{slash}DSR)") (class "Default")
      (node (ref "DSR") (pin "TP") (pinfunction "TP_TP") (pintype "input"))
      (node (ref "U$2") (pin "B2") (pinfunction "C107/DSR_B2") (pintype "bidirectional"))
    )
    (net (code "58") (name "Net-(U$2-C108{slash}DTR)") (class "Default")
      (node (ref "DTR") (pin "TP") (pinfunction "TP_TP") (pintype "input"))
      (node (ref "U$2") (pin "B3") (pinfunction "C108/DTR_B3") (pintype "bidirectional"))
    )
    (net (code "59") (name "Net-(U$2-C109{slash}DCD)") (class "Default")
      (node (ref "DCD") (pin "TP") (pinfunction "TP_TP") (pintype "input"))
      (node (ref "U$2") (pin "B5") (pinfunction "C109/DCD_B5") (pintype "bidirectional"))
    )
    (net (code "60") (name "Net-(U$2-C125{slash}RING)") (class "Default")
      (node (ref "RING") (pin "TP") (pinfunction "TP_TP") (pintype "input"))
      (node (ref "U$2") (pin "B4") (pinfunction "C125/RING_B4") (pintype "bidirectional"))
    )
    (net (code "61") (name "Net-(U$2-DAC_OUT)") (class "Default")
      (node (ref "DACO") (pin "TP") (pinfunction "TP_TP") (pintype "input"))
      (node (ref "U$2") (pin "G7") (pinfunction "DAC_OUT_G7") (pintype "bidirectional"))
    )
    (net (code "62") (name "Net-(U$2-EAR+)") (class "Default")
      (node (ref "EAR+") (pin "TP") (pinfunction "TP_TP") (pintype "input"))
      (node (ref "U$2") (pin "D8") (pinfunction "EAR+_D8") (pintype "bidirectional"))
    )
    (net (code "63") (name "Net-(U$2-EAR-)") (class "Default")
      (node (ref "EAR-") (pin "TP") (pinfunction "TP_TP") (pintype "input"))
      (node (ref "U$2") (pin "E8") (pinfunction "EAR-_E8") (pintype "bidirectional"))
    )
    (net (code "64") (name "Net-(U$2-GPIO_01)") (class "Default")
      (node (ref "IO1") (pin "TP") (pinfunction "TP_TP") (pintype "input"))
      (node (ref "U$2") (pin "D3") (pinfunction "GPIO_01_D3") (pintype "bidirectional"))
    )
    (net (code "65") (name "Net-(U$2-GPIO_02{slash}JDR)") (class "Default")
      (node (ref "IO2") (pin "TP") (pinfunction "TP_TP") (pintype "input"))
      (node (ref "U$2") (pin "D2") (pinfunction "GPIO_02/JDR_D2") (pintype "bidirectional"))
    )
    (net (code "66") (name "Net-(U$2-GPIO_03)") (class "Default")
      (node (ref "IO3") (pin "TP") (pinfunction "TP_TP") (pintype "input"))
      (node (ref "U$2") (pin "E4") (pinfunction "GPIO_03_E4") (pintype "bidirectional"))
    )
    (net (code "67") (name "Net-(U$2-GPIO_04{slash}TX_DISAB)") (class "Default")
      (node (ref "IO4") (pin "TP") (pinfunction "TP_TP") (pintype "input"))
      (node (ref "U$2") (pin "H7") (pinfunction "GPIO_04/TX_DISAB_H7") (pintype "bidirectional"))
    )
    (net (code "68") (name "Net-(U$2-GPIO_05{slash}RFTXMON)") (class "Default")
      (node (ref "IO5") (pin "TP") (pinfunction "TP_TP") (pintype "input"))
      (node (ref "U$2") (pin "G2") (pinfunction "GPIO_05/RFTXMON_G2") (pintype "bidirectional"))
    )
    (net (code "69") (name "Net-(U$2-GPIO_06{slash}ALARM)") (class "Default")
      (node (ref "IO6") (pin "TP") (pinfunction "TP_TP") (pintype "input"))
      (node (ref "U$2") (pin "H8") (pinfunction "GPIO_06/ALARM_H8") (pintype "bidirectional"))
    )
    (net (code "70") (name "Net-(U$2-GPIO_07{slash}BUZZER)") (class "Default")
      (node (ref "IO7") (pin "TP") (pinfunction "TP_TP") (pintype "input"))
      (node (ref "U$2") (pin "G6") (pinfunction "GPIO_07/BUZZER_G6") (pintype "bidirectional"))
    )
    (net (code "71") (name "Net-(U$2-GPIO_08)") (class "Default")
      (node (ref "IO8") (pin "TP") (pinfunction "TP_TP") (pintype "input"))
      (node (ref "U$2") (pin "D4") (pinfunction "GPIO_08_D4") (pintype "bidirectional"))
    )
    (net (code "72") (name "Net-(U$2-GPIO_09)") (class "Default")
      (node (ref "IO9") (pin "TP") (pinfunction "TP_TP") (pintype "input"))
      (node (ref "U$2") (pin "F4") (pinfunction "GPIO_09_F4") (pintype "bidirectional"))
    )
    (net (code "73") (name "Net-(U$2-GPIO_10)") (class "Default")
      (node (ref "IO10") (pin "TP") (pinfunction "TP_TP") (pintype "input"))
      (node (ref "U$2") (pin "E3") (pinfunction "GPIO_10_E3") (pintype "bidirectional"))
    )
    (net (code "74") (name "Net-(U$2-MIC+)") (class "Default")
      (node (ref "MIC+") (pin "TP") (pinfunction "TP_TP") (pintype "input"))
      (node (ref "U$2") (pin "B8") (pinfunction "MIC+_B8") (pintype "bidirectional"))
    )
    (net (code "75") (name "Net-(U$2-MIC-)") (class "Default")
      (node (ref "MIC-") (pin "TP") (pinfunction "TP_TP") (pintype "input"))
      (node (ref "U$2") (pin "C8") (pinfunction "MIC-_C8") (pintype "bidirectional"))
    )
    (net (code "76") (name "Net-(U$2-RESET)") (class "Default")
      (node (ref "RST") (pin "TP") (pinfunction "TP_TP") (pintype "input"))
      (node (ref "U$2") (pin "C1") (pinfunction "RESET_C1") (pintype "bidirectional"))
    )
    (net (code "77") (name "Net-(U$2-SIMIN)") (class "Default")
      (node (ref "R33") (pin "2") (pinfunction "2_2") (pintype "passive"))
      (node (ref "U$2") (pin "B7") (pinfunction "SIMIN_B7") (pintype "bidirectional"))
    )
    (net (code "78") (name "Net-(U$2-STAT_LED)") (class "Default")
      (node (ref "STAT") (pin "TP") (pinfunction "TP_TP") (pintype "input"))
      (node (ref "U$2") (pin "G8") (pinfunction "STAT_LED_G8") (pintype "bidirectional"))
    )
    (net (code "79") (name "Net-(U$2-VRTC)") (class "Default")
      (node (ref "U$2") (pin "H2") (pinfunction "VRTC_H2") (pintype "bidirectional"))
      (node (ref "VRTC") (pin "TP") (pinfunction "TP_TP") (pintype "input"))
    )
    (net (code "80") (name "Net-(U$4-CTS{slash}SPI_CLK{slash}MODE)") (class "Default")
      (node (ref "TP9") (pin "TP") (pinfunction "TP_TP") (pintype "input"))
      (node (ref "U$4") (pin "1") (pinfunction "CTS/SPI_CLK/MODE_1") (pintype "bidirectional"))
    )
    (net (code "81") (name "Net-(U$4-FLASH_ENABLE)") (class "Default")
      (node (ref "TP26") (pin "TP") (pinfunction "TP_TP") (pintype "input"))
      (node (ref "U$4") (pin "8") (pinfunction "FLASH_ENABLE_8") (pintype "bidirectional"))
    )
    (net (code "82") (name "Net-(U$4-GPIO3)") (class "Default")
      (node (ref "TP27") (pin "TP") (pinfunction "TP_TP") (pintype "input"))
      (node (ref "U$4") (pin "9") (pinfunction "GPIO3_9") (pintype "bidirectional"))
    )
    (net (code "83") (name "Net-(U$4-RTC_IN)") (class "Default")
      (node (ref "TP28") (pin "TP") (pinfunction "TP_TP") (pintype "input"))
      (node (ref "U$4") (pin "10") (pinfunction "RTC_IN_10") (pintype "bidirectional"))
    )
    (net (code "84") (name "Net-(U$4-SPI_CS{slash}RTS{slash}GPIO7)") (class "Default")
      (node (ref "TP10") (pin "TP") (pinfunction "TP_TP") (pintype "input"))
      (node (ref "U$4") (pin "4") (pinfunction "SPI_CS/RTS/GPIO7_4") (pintype "bidirectional"))
    )
    (net (code "85") (name "Net-(U$7-BP)") (class "Default")
      (node (ref "C3") (pin "1") (pinfunction "1_1") (pintype "passive"))
      (node (ref "U$7") (pin "4") (pinfunction "BP_4") (pintype "input"))
    )
    (net (code "86") (name "Net-(U$14-FB)") (class "Default")
      (node (ref "C20") (pin "2") (pinfunction "2_2") (pintype "passive"))
      (node (ref "R3") (pin "1") (pinfunction "1_1") (pintype "passive"))
      (node (ref "R6") (pin "2") (pinfunction "2_2") (pintype "passive"))
      (node (ref "U$14") (pin "3") (pinfunction "FB_3") (pintype "bidirectional"))
    )
    (net (code "87") (name "Net-(U$70-PROG)") (class "Default")
      (node (ref "R7") (pin "1") (pinfunction "1_1") (pintype "passive"))
      (node (ref "U$70") (pin "5") (pinfunction "PROG_5") (pintype "bidirectional"))
    )
    (net (code "88") (name "Net-(U$70-STAT)") (class "Default")
      (node (ref "R4") (pin "2") (pinfunction "2_2") (pintype "passive"))
      (node (ref "U$70") (pin "1") (pinfunction "STAT_1") (pintype "bidirectional"))
    )
    (net (code "89") (name "PUSH_BUTTON") (class "Default")
      (node (ref "R31") (pin "1") (pinfunction "1_1") (pintype "passive"))
      (node (ref "U$11") (pin "NO") (pinfunction "NO_NO") (pintype "bidirectional"))
      (node (ref "U$20") (pin "C6") (pinfunction "P1.15/ENET-RX_CLK_C6") (pintype "bidirectional"))
    )
    (net (code "90") (name "PWRMON") (class "Default")
      (node (ref "PMON") (pin "TP") (pinfunction "TP_TP") (pintype "input"))
      (node (ref "U$2") (pin "E2") (pinfunction "PWRMON_E2") (pintype "bidirectional"))
      (node (ref "U$20") (pin "K10") (pinfunction "P2.12/EINT2N/I2STX_WS_K10") (pintype "bidirectional"))
    )
    (net (code "91") (name "RES") (class "Default")
      (node (ref "U$20") (pin "A8") (pinfunction "P0.4/I2SRX_CLK/CAN_RX2/CAP2.0_A8") (pintype "bidirectional"))
      (node (ref "U$5") (pin "21") (pinfunction "RES_21") (pintype "bidirectional"))
    )
    (net (code "92") (name "RESET") (class "Default")
      (node (ref "IC1") (pin "28") (pinfunction "DTR_28") (pintype "output"))
      (node (ref "TP2") (pin "TP") (pinfunction "TP_TP") (pintype "input"))
    )
    (net (code "93") (name "ROTA") (class "Default")
      (node (ref "R17") (pin "1") (pinfunction "1_1") (pintype "passive"))
      (node (ref "U$11") (pin "A") (pinfunction "A_A") (pintype "bidirectional"))
      (node (ref "U$20") (pin "D6") (pinfunction "P1.14/ENET-RX_ER_D6") (pintype "bidirectional"))
    )
    (net (code "94") (name "ROTB") (class "Default")
      (node (ref "R18") (pin "1") (pinfunction "1_1") (pintype "passive"))
      (node (ref "U$11") (pin "B") (pinfunction "B_B") (pintype "bidirectional"))
      (node (ref "U$20") (pin "A5") (pinfunction "P1.10/ENET_RXD1_A5") (pintype "bidirectional"))
    )
    (net (code "95") (name "RTS1") (class "Default")
      (node (ref "U$20") (pin "E9") (pinfunction "P2.7/CAN_RX2/RTS1_E9") (pintype "bidirectional"))
    )
    (net (code "96") (name "RXD0") (class "Default")
      (node (ref "IC1") (pin "26") (pinfunction "TXD_26") (pintype "output"))
      (node (ref "TP15") (pin "TP") (pinfunction "TP_TP") (pintype "input"))
      (node (ref "U$20") (pin "A2") (pinfunction "P0.3/RXD0/AD0.6_A2") (pintype "bidirectional"))
    )
    (net (code "97") (name "RXD3") (class "Default")
      (node (ref "U$20") (pin "E6") (pinfunction "P4.29/TX_MCLK/MAT2.1/RXD3_E6") (pintype "bidirectional"))
    )
    (net (code "98") (name "R{slash}W") (class "Default")
      (node (ref "U$20") (pin "K8") (pinfunction "P0.0/CAN_RX1/TXD3/SDA1_K8") (pintype "bidirectional"))
    )
    (net (code "99") (name "SCK") (class "Default")
      (node (ref "U$20") (pin "F10") (pinfunction "P0.15/TXD1/SCK0/SCK_F10") (pintype "bidirectional"))
      (node (ref "U$64") (pin "5") (pinfunction "5-SCK_5") (pintype "bidirectional"))
    )
    (net (code "100") (name "SCL") (class "Default")
      (node (ref "R11") (pin "1") (pinfunction "1_1") (pintype "passive"))
      (node (ref "U$20") (pin "J1") (pinfunction "P0.28/SCL0/USB_SCL_J1") (pintype "bidirectional"))
    )
    (net (code "101") (name "SDA") (class "Default")
      (node (ref "R10") (pin "1") (pinfunction "1_1") (pintype "passive"))
      (node (ref "U$20") (pin "J2") (pinfunction "P0.27/SDA0/USB_SDA_J2") (pintype "bidirectional"))
    )
    (net (code "102") (name "SIMCLK") (class "Default")
      (node (ref "U$17") (pin "C3") (pinfunction "3-CLK_C3") (pintype "bidirectional"))
      (node (ref "U$2") (pin "A5") (pinfunction "SIMCLK_A5") (pintype "bidirectional"))
    )
    (net (code "103") (name "SIMIO") (class "Default")
      (node (ref "U$17") (pin "C7") (pinfunction "7-IO_C7") (pintype "bidirectional"))
      (node (ref "U$2") (pin "A6") (pinfunction "SIMIO_A6") (pintype "bidirectional"))
    )
    (net (code "104") (name "SIMRST") (class "Default")
      (node (ref "U$17") (pin "C2") (pinfunction "2-RST_C2") (pintype "bidirectional"))
      (node (ref "U$2") (pin "A8") (pinfunction "SIMRST_A8") (pintype "bidirectional"))
    )
    (net (code "105") (name "SIMVCC") (class "Default")
      (node (ref "U$17") (pin "C1") (pinfunction "1-VCC_C1") (pintype "bidirectional"))
      (node (ref "U$2") (pin "A7") (pinfunction "SIMVCC_A7") (pintype "bidirectional"))
    )
    (net (code "106") (name "TGT_NRESET") (class "Default")
      (node (ref "C29") (pin "2") (pinfunction "P$2_2") (pintype "passive"))
      (node (ref "R30") (pin "1") (pinfunction "P$1_1") (pintype "passive"))
      (node (ref "U$16") (pin "1") (pinfunction "1_1") (pintype "passive"))
      (node (ref "U$20") (pin "F3") (pinfunction "NRESET_F3") (pintype "bidirectional"))
    )
    (net (code "107") (name "TGT_RTCK") (class "Default")
      (node (ref "U$20") (pin "B2") (pinfunction "RTCK_B2") (pintype "bidirectional"))
    )
    (net (code "108") (name "TGT_SBL_ISP") (class "Default")
      (node (ref "TP1") (pin "TP") (pinfunction "TP_TP") (pintype "input"))
      (node (ref "U$18") (pin "2") (pinfunction "2_2") (pintype "bidirectional"))
      (node (ref "U$20") (pin "J10") (pinfunction "P2.10/EINT0N/NMI_J10") (pintype "bidirectional"))
    )
    (net (code "109") (name "TGT_TCK") (class "Default")
      (node (ref "U$20") (pin "C1") (pinfunction "TCK/SWDCLK_C1") (pintype "bidirectional"))
    )
    (net (code "110") (name "TGT_TDI") (class "Default")
      (node (ref "U$20") (pin "C3") (pinfunction "TDI_C3") (pintype "bidirectional"))
    )
    (net (code "111") (name "TGT_TDO") (class "Default")
      (node (ref "U$20") (pin "A1") (pinfunction "TDO/SWO_A1") (pintype "bidirectional"))
    )
    (net (code "112") (name "TGT_TMS") (class "Default")
      (node (ref "U$20") (pin "B1") (pinfunction "TMS/SWDIO_B1") (pintype "bidirectional"))
    )
    (net (code "113") (name "TGT_TRST") (class "Default")
      (node (ref "U$20") (pin "C2") (pinfunction "TRST_N_C2") (pintype "bidirectional"))
    )
    (net (code "114") (name "TXD0") (class "Default")
      (node (ref "IC1") (pin "25") (pinfunction "RXD_25") (pintype "input"))
      (node (ref "TP16") (pin "TP") (pinfunction "TP_TP") (pintype "input"))
      (node (ref "U$20") (pin "C4") (pinfunction "P0.2/TXD0/AD0.7_C4") (pintype "bidirectional"))
    )
    (net (code "115") (name "TXD3") (class "Default")
      (node (ref "U$20") (pin "C7") (pinfunction "P4.28/RX_MCLK/MAT2.0/TXD3_C7") (pintype "bidirectional"))
    )
    (net (code "116") (name "USB_BUS") (class "Default")
      (node (ref "C8") (pin "1") (pinfunction "1_1") (pintype "passive"))
      (node (ref "IC1") (pin "7") (pinfunction "REGIN_7") (pintype "passive"))
      (node (ref "IC1") (pin "8") (pinfunction "VBUS_8") (pintype "input"))
      (node (ref "LED1") (pin "A") (pinfunction "A_A") (pintype "passive"))
      (node (ref "U$69") (pin "1") (pinfunction "VCC_1") (pintype "bidirectional"))
      (node (ref "U$70") (pin "4") (pinfunction "VDD_4") (pintype "bidirectional"))
    )
    (net (code "117") (name "VBATT") (class "Default")
      (node (ref "C18") (pin "1") (pinfunction "1_1") (pintype "passive"))
      (node (ref "C32") (pin "1") (pinfunction "1_1") (pintype "passive"))
      (node (ref "C4") (pin "1") (pinfunction "1_1") (pintype "passive"))
      (node (ref "C5") (pin "1") (pinfunction "1_1") (pintype "passive"))
      (node (ref "TP11") (pin "TP") (pinfunction "TP_TP") (pintype "input"))
      (node (ref "U$1") (pin "1") (pinfunction "IN_1") (pintype "input"))
      (node (ref "U$14") (pin "4") (pinfunction "EN_4") (pintype "bidirectional"))
      (node (ref "U$14") (pin "5") (pinfunction "VIN_5") (pintype "bidirectional"))
      (node (ref "U$15") (pin "1") (pinfunction "1_1") (pintype "passive"))
      (node (ref "U$2") (pin "F1") (pinfunction "VBATT_F1") (pintype "bidirectional"))
      (node (ref "U$2") (pin "F2") (pinfunction "VBATT_F2") (pintype "bidirectional"))
      (node (ref "U$2") (pin "F3") (pinfunction "VBATT_F3") (pintype "bidirectional"))
      (node (ref "U$7") (pin "1") (pinfunction "IN_1") (pintype "input"))
      (node (ref "U$7") (pin "3") (pinfunction "EN_3") (pintype "input"))
      (node (ref "U$70") (pin "3") (pinfunction "VBAT_3") (pintype "bidirectional"))
    )
    (net (code "118") (name "VBREF") (class "Default")
      (node (ref "C6") (pin "1") (pinfunction "1_1") (pintype "passive"))
      (node (ref "U$5") (pin "26") (pinfunction "VBREF_26") (pintype "bidirectional"))
    )
    (net (code "119") (name "VCC") (class "Default")
      (node (ref "C10") (pin "2") (pinfunction "2_2") (pintype "passive"))
      (node (ref "C11") (pin "1") (pinfunction "P$1_1") (pintype "passive"))
      (node (ref "C12") (pin "1") (pinfunction "P$1_1") (pintype "passive"))
      (node (ref "C13") (pin "1") (pinfunction "P$1_1") (pintype "passive"))
      (node (ref "C14") (pin "1") (pinfunction "P$1_1") (pintype "passive"))
      (node (ref "C2") (pin "1") (pinfunction "1_1") (pintype "passive"))
      (node (ref "C24") (pin "1") (pinfunction "1_1") (pintype "passive"))
      (node (ref "C27") (pin "1") (pinfunction "1_1") (pintype "passive"))
      (node (ref "C28") (pin "2") (pinfunction "P$2_2") (pintype "passive"))
      (node (ref "L2") (pin "P$1") (pinfunction "P$1_P$1") (pintype "bidirectional"))
      (node (ref "OSC3") (pin "P$1") (pinfunction "EN_P$1") (pintype "bidirectional"))
      (node (ref "OSC3") (pin "P$4") (pinfunction "VCC_P$4") (pintype "bidirectional"))
      (node (ref "R10") (pin "2") (pinfunction "2_2") (pintype "passive"))
      (node (ref "R11") (pin "2") (pinfunction "2_2") (pintype "passive"))
      (node (ref "R17") (pin "2") (pinfunction "2_2") (pintype "passive"))
      (node (ref "R18") (pin "2") (pinfunction "2_2") (pintype "passive"))
      (node (ref "R30") (pin "2") (pinfunction "P$2_2") (pintype "passive"))
      (node (ref "R31") (pin "2") (pinfunction "2_2") (pintype "passive"))
      (node (ref "U$20") (pin "A3") (pinfunction "VDD3.3V_A3") (pintype "bidirectional"))
      (node (ref "U$20") (pin "A7") (pinfunction "VDDREG3.3V_A7") (pintype "bidirectional"))
      (node (ref "U$20") (pin "C10") (pinfunction "VDD3.3V_C10") (pintype "bidirectional"))
      (node (ref "U$20") (pin "D4") (pinfunction "NC_D4") (pintype "bidirectional"))
      (node (ref "U$20") (pin "H6") (pinfunction "VDDREG3.3V_H6") (pintype "bidirectional"))
      (node (ref "U$20") (pin "H9") (pinfunction "VDD3.3V_H9") (pintype "bidirectional"))
      (node (ref "U$20") (pin "K2") (pinfunction "VDD3.3V_K2") (pintype "bidirectional"))
      (node (ref "U$5") (pin "17") (pinfunction "BS1_17") (pintype "bidirectional"))
      (node (ref "U$5") (pin "18") (pinfunction "BS2_18") (pintype "bidirectional"))
      (node (ref "U$5") (pin "27") (pinfunction "VDD_27") (pintype "bidirectional"))
      (node (ref "U$5") (pin "4") (pinfunction "VDDIO_4") (pintype "bidirectional"))
      (node (ref "U$64") (pin "4") (pinfunction "4-VDD_4") (pintype "bidirectional"))
      (node (ref "U$7") (pin "5") (pinfunction "OUT_5") (pintype "passive"))
    )
    (net (code "120") (name "VCC_1.8") (class "Default")
      (node (ref "C30") (pin "1") (pinfunction "1_1") (pintype "passive"))
      (node (ref "R12") (pin "2") (pinfunction "2_2") (pintype "passive"))
      (node (ref "U$1") (pin "5") (pinfunction "OUT_5") (pintype "passive"))
      (node (ref "U$4") (pin "12") (pinfunction "VCC_12") (pintype "bidirectional"))
    )
    (net (code "121") (name "VCC_1.8_EN") (class "Default")
      (node (ref "U$1") (pin "3") (pinfunction "EN_3") (pintype "input"))
      (node (ref "U$20") (pin "F5") (pinfunction "P1.21/MCABORT/PWM1.3/SSEL0_F5") (pintype "bidirectional"))
    )
    (net (code "122") (name "VCC_2.8_EN") (class "Default")
      (node (ref "U$20") (pin "F4") (pinfunction "P1.31/SCK1/AD0.5_F4") (pintype "bidirectional"))
    )
    (net (code "123") (name "VCC_LED") (class "Default")
      (node (ref "C19") (pin "1") (pinfunction "1_1") (pintype "passive"))
      (node (ref "C20") (pin "1") (pinfunction "1_1") (pintype "passive"))
      (node (ref "C26") (pin "1") (pinfunction "1_1") (pintype "passive"))
      (node (ref "D2") (pin "2") (pinfunction "C_2") (pintype "passive"))
      (node (ref "R3") (pin "2") (pinfunction "2_2") (pintype "passive"))
      (node (ref "U$5") (pin "2") (pinfunction "VCC1_2") (pintype "bidirectional"))
      (node (ref "U$5") (pin "29") (pinfunction "VCC2_29") (pintype "bidirectional"))
    )
    (net (code "124") (name "VCOMH") (class "Default")
      (node (ref "C22") (pin "1") (pinfunction "1_1") (pintype "passive"))
      (node (ref "C25") (pin "1") (pinfunction "1_1") (pintype "passive"))
      (node (ref "U$5") (pin "3") (pinfunction "VCOMH_3") (pintype "bidirectional"))
    )
    (net (code "125") (name "VDD") (class "Default")
      (node (ref "IC1") (pin "6") (pinfunction "VDD_6") (pintype "power_in"))
      (node (ref "R5") (pin "2") (pinfunction "2_2") (pintype "passive"))
      (node (ref "TP21") (pin "TP") (pinfunction "TP_TP") (pintype "input"))
    )
    (net (code "126") (name "VPA") (class "Default")
      (node (ref "C7") (pin "1") (pinfunction "1_1") (pintype "passive"))
      (node (ref "U$5") (pin "25") (pinfunction "VPA_25") (pintype "bidirectional"))
    )
    (net (code "127") (name "VPB") (class "Default")
      (node (ref "C21") (pin "1") (pinfunction "1_1") (pintype "passive"))
      (node (ref "U$5") (pin "24") (pinfunction "VPB_24") (pintype "bidirectional"))
    )
    (net (code "128") (name "VPC") (class "Default")
      (node (ref "C1") (pin "1") (pinfunction "1_1") (pintype "passive"))
      (node (ref "U$5") (pin "23") (pinfunction "VPC_23") (pintype "bidirectional"))
    )
    (net (code "129") (name "VSL") (class "Default")
      (node (ref "R9") (pin "2") (pinfunction "2_2") (pintype "passive"))
      (node (ref "U$5") (pin "5") (pinfunction "VSL_5") (pintype "bidirectional"))
    )
    (net (code "130") (name "unconnected-(IC1-~{SUSPEND}-Pad11)") (class "Default")
      (node (ref "IC1") (pin "11") (pinfunction "~{SUSPEND}_11") (pintype "output"))
    )
    (net (code "131") (name "unconnected-(U$2-RXD_AUX-PadE1)") (class "Default")
      (node (ref "U$2") (pin "E1") (pinfunction "RXD_AUX_E1") (pintype "bidirectional"))
    )
    (net (code "132") (name "unconnected-(U$2-TXD_AUX-PadD1)") (class "Default")
      (node (ref "U$2") (pin "D1") (pinfunction "TXD_AUX_D1") (pintype "bidirectional"))
    )
    (net (code "133") (name "unconnected-(U$5-D2-Pad12)") (class "Default")
      (node (ref "U$5") (pin "12") (pinfunction "D2_12") (pintype "bidirectional"))
    )
    (net (code "134") (name "unconnected-(U$5-NC1-Pad1)") (class "Default")
      (node (ref "U$5") (pin "1") (pinfunction "NC1_1") (pintype "bidirectional"))
    )
    (net (code "135") (name "unconnected-(U$5-NC2-Pad30)") (class "Default")
      (node (ref "U$5") (pin "30") (pinfunction "NC2_30") (pintype "bidirectional"))
    )
    (net (code "136") (name "unconnected-(U$17-4-RSVD-PadP$1)") (class "Default")
      (node (ref "U$17") (pin "P$1") (pinfunction "4-RSVD_P$1") (pintype "bidirectional"))
    )
    (net (code "137") (name "unconnected-(U$17-6-VPP-PadC6)") (class "Default")
      (node (ref "U$17") (pin "C6") (pinfunction "6-VPP_C6") (pintype "bidirectional"))
    )
    (net (code "138") (name "unconnected-(U$17-8-RSVD-PadP$2)") (class "Default")
      (node (ref "U$17") (pin "P$2") (pinfunction "8-RSVD_P$2") (pintype "bidirectional"))
    )
    (net (code "139") (name "unconnected-(U$18-Pad1)") (class "Default")
      (node (ref "U$18") (pin "1") (pinfunction "1_1") (pintype "bidirectional"))
    )
    (net (code "140") (name "unconnected-(U$20-P0.10{slash}TXD2{slash}SDA2{slash}MAT3.0-PadH7)") (class "Default")
      (node (ref "U$20") (pin "H7") (pinfunction "P0.10/TXD2/SDA2/MAT3.0_H7") (pintype "bidirectional"))
    )
    (net (code "141") (name "unconnected-(U$20-P0.19{slash}DSR1{slash}MCICLK{slash}SDA1-PadG10)") (class "Default")
      (node (ref "U$20") (pin "G10") (pinfunction "P0.19/DSR1/MCICLK/SDA1_G10") (pintype "bidirectional"))
    )
    (net (code "142") (name "unconnected-(U$20-P0.20{slash}DTR1{slash}SCL1-PadG9)") (class "Default")
      (node (ref "U$20") (pin "G9") (pinfunction "P0.20/DTR1/SCL1_G9") (pintype "bidirectional"))
    )
    (net (code "143") (name "unconnected-(U$20-P0.21{slash}RI1{slash}CAN_RX1-PadG8)") (class "Default")
      (node (ref "U$20") (pin "G8") (pinfunction "P0.21/RI1/CAN_RX1_G8") (pintype "bidirectional"))
    )
    (net (code "144") (name "unconnected-(U$20-P0.22{slash}RTS1{slash}CAN_TX1-PadH10)") (class "Default")
      (node (ref "U$20") (pin "H10") (pinfunction "P0.22/RTS1/CAN_TX1_H10") (pintype "bidirectional"))
    )
    (net (code "145") (name "unconnected-(U$20-P0.23{slash}AD0.0{slash}I2SRX_CLK{slash}CAP3.0-PadE5)") (class "Default")
      (node (ref "U$20") (pin "E5") (pinfunction "P0.23/AD0.0/I2SRX_CLK/CAP3.0_E5") (pintype "bidirectional"))
    )
    (net (code "146") (name "unconnected-(U$20-P0.24{slash}AD0.1{slash}I2SRX_WS{slash}CAP3.1-PadD1)") (class "Default")
      (node (ref "U$20") (pin "D1") (pinfunction "P0.24/AD0.1/I2SRX_WS/CAP3.1_D1") (pintype "bidirectional"))
    )
    (net (code "147") (name "unconnected-(U$20-P0.25{slash}AD0.2{slash}I2SRX_SDA{slash}TXD3-PadD2)") (class "Default")
      (node (ref "U$20") (pin "D2") (pinfunction "P0.25/AD0.2/I2SRX_SDA/TXD3_D2") (pintype "bidirectional"))
    )
    (net (code "148") (name "unconnected-(U$20-P0.26{slash}AD0.3{slash}AOUT{slash}RXD3-PadD3)") (class "Default")
      (node (ref "U$20") (pin "D3") (pinfunction "P0.26/AD0.3/AOUT/RXD3_D3") (pintype "bidirectional"))
    )
    (net (code "149") (name "unconnected-(U$20-P0.30{slash}USB_D--PadG4)") (class "Default")
      (node (ref "U$20") (pin "G4") (pinfunction "P0.30/USB_D-_G4") (pintype "bidirectional"))
    )
    (net (code "150") (name "unconnected-(U$20-P1.4{slash}ENET-TX_EN-PadA4)") (class "Default")
      (node (ref "U$20") (pin "A4") (pinfunction "P1.4/ENET-TX_EN_A4") (pintype "bidirectional"))
    )
    (net (code "151") (name "unconnected-(U$20-P1.8{slash}ENET_CRS-PadC5)") (class "Default")
      (node (ref "U$20") (pin "C5") (pinfunction "P1.8/ENET_CRS_C5") (pintype "bidirectional"))
    )
    (net (code "152") (name "unconnected-(U$20-P1.9{slash}ENET_RXD0-PadB5)") (class "Default")
      (node (ref "U$20") (pin "B5") (pinfunction "P1.9/ENET_RXD0_B5") (pintype "bidirectional"))
    )
    (net (code "153") (name "unconnected-(U$20-P1.16{slash}ENET-MDC-PadA6)") (class "Default")
      (node (ref "U$20") (pin "A6") (pinfunction "P1.16/ENET-MDC_A6") (pintype "bidirectional"))
    )
    (net (code "154") (name "unconnected-(U$20-P1.17{slash}ENET-MDIO-PadB6)") (class "Default")
      (node (ref "U$20") (pin "B6") (pinfunction "P1.17/ENET-MDIO_B6") (pintype "bidirectional"))
    )
    (net (code "155") (name "unconnected-(U$20-P1.18{slash}USB_UP{slash}PWM1.1{slash}CAP1.0-PadH4)") (class "Default")
      (node (ref "U$20") (pin "H4") (pinfunction "P1.18/USB_UP/PWM1.1/CAP1.0_H4") (pintype "bidirectional"))
    )
    (net (code "156") (name "unconnected-(U$20-P1.22{slash}MC0B{slash}USB_PWRD{slash}MAT1.0-PadJ5)") (class "Default")
      (node (ref "U$20") (pin "J5") (pinfunction "P1.22/MC0B/USB_PWRD/MAT1.0_J5") (pintype "bidirectional"))
    )
    (net (code "157") (name "unconnected-(U$20-P1.25{slash}MC1A{slash}MAT1.1-PadG5)") (class "Default")
      (node (ref "U$20") (pin "G5") (pinfunction "P1.25/MC1A/MAT1.1_G5") (pintype "bidirectional"))
    )
    (net (code "158") (name "unconnected-(U$20-P1.26{slash}MC1B{slash}PWM1.6{slash}CAP0.0-PadK6)") (class "Default")
      (node (ref "U$20") (pin "K6") (pinfunction "P1.26/MC1B/PWM1.6/CAP0.0_K6") (pintype "bidirectional"))
    )
    (net (code "159") (name "unconnected-(U$20-P1.27{slash}CLKOUT{slash}USB_OVRCR{slash}CAP0.1-PadK7)") (class "Default")
      (node (ref "U$20") (pin "K7") (pinfunction "P1.27/CLKOUT/USB_OVRCR/CAP0.1_K7") (pintype "bidirectional"))
    )
    (net (code "160") (name "unconnected-(U$20-P1.28{slash}MC2A{slash}PCAP1.0{slash}MAT0.0-PadJ7)") (class "Default")
      (node (ref "U$20") (pin "J7") (pinfunction "P1.28/MC2A/PCAP1.0/MAT0.0_J7") (pintype "bidirectional"))
    )
    (net (code "161") (name "unconnected-(U$20-P1.30{slash}VBUS{slash}AD0.4-PadH1)") (class "Default")
      (node (ref "U$20") (pin "H1") (pinfunction "P1.30/VBUS/AD0.4_H1") (pintype "bidirectional"))
    )
    (net (code "162") (name "unconnected-(U$20-P2.6{slash}PCAP1.0{slash}RI1{slash}TRACECLK-PadE8)") (class "Default")
      (node (ref "U$20") (pin "E8") (pinfunction "P2.6/PCAP1.0/RI1/TRACECLK_E8") (pintype "bidirectional"))
    )
    (net (code "163") (name "unconnected-(U$20-P2.11{slash}EINT1N{slash}I2STX_CLK-PadH8)") (class "Default")
      (node (ref "U$20") (pin "H8") (pinfunction "P2.11/EINT1N/I2STX_CLK_H8") (pintype "bidirectional"))
    )
    (net (code "164") (name "unconnected-(U$20-P2.13{slash}EINT3N{slash}I2STX_SDA-PadJ9)") (class "Default")
      (node (ref "U$20") (pin "J9") (pinfunction "P2.13/EINT3N/I2STX_SDA_J9") (pintype "bidirectional"))
    )
    (net (code "165") (name "unconnected-(U$20-P3.25{slash}MAT0.0{slash}PWM1.2-PadH3)") (class "Default")
      (node (ref "U$20") (pin "H3") (pinfunction "P3.25/MAT0.0/PWM1.2_H3") (pintype "bidirectional"))
    )
    (net (code "166") (name "unconnected-(U$20-P3.26{slash}STCLK{slash}MAT0.1{slash}PWM1.3-PadK1)") (class "Default")
      (node (ref "U$20") (pin "K1") (pinfunction "P3.26/STCLK/MAT0.1/PWM1.3_K1") (pintype "bidirectional"))
    )
    (net (code "167") (name "unconnected-(U$20-RSTOUTN-PadE4)") (class "Default")
      (node (ref "U$20") (pin "E4") (pinfunction "RSTOUTN_E4") (pintype "bidirectional"))
    )
    (net (code "168") (name "unconnected-(U$20-VBAT-PadG2)") (class "Default")
      (node (ref "U$20") (pin "G2") (pinfunction "VBAT_G2") (pintype "bidirectional"))
    )
    (net (code "169") (name "unconnected-(U$20-X2-PadG3)") (class "Default")
      (node (ref "U$20") (pin "G3") (pinfunction "X2_G3") (pintype "bidirectional"))
    )
    (net (code "170") (name "unconnected-(U$64-1-{slash}CS-Pad1)") (class "Default")
      (node (ref "U$64") (pin "1") (pinfunction "1-/CS_1") (pintype "bidirectional"))
    )
    (net (code "171") (name "unconnected-(U$64-NC-Pad8)") (class "Default")
      (node (ref "U$64") (pin "8") (pinfunction "NC_8") (pintype "bidirectional"))
    )
    (net (code "172") (name "unconnected-(U$69-ID-Pad4)") (class "Default")
      (node (ref "U$69") (pin "4") (pinfunction "ID_4") (pintype "bidirectional"))
    )
    (net (code "173") (name "{slash}PGOOD") (class "Default")
      (node (ref "U$20") (pin "K4") (pinfunction "P1.20/MCFB0/PWM1.2/SCK0_K4") (pintype "bidirectional"))
    )
    (net (code "174") (name "{slash}SS") (class "Default")
      (node (ref "U$20") (pin "F8") (pinfunction "P0.16/RXD1/SSEL0/SSEL_F8") (pintype "bidirectional"))
      (node (ref "U$64") (pin "2") (pinfunction "2-DI_2") (pintype "bidirectional"))
    )
  )
)
